# nexusqfp.net
KiCad netlist of a schematic drawn in Altium Designer
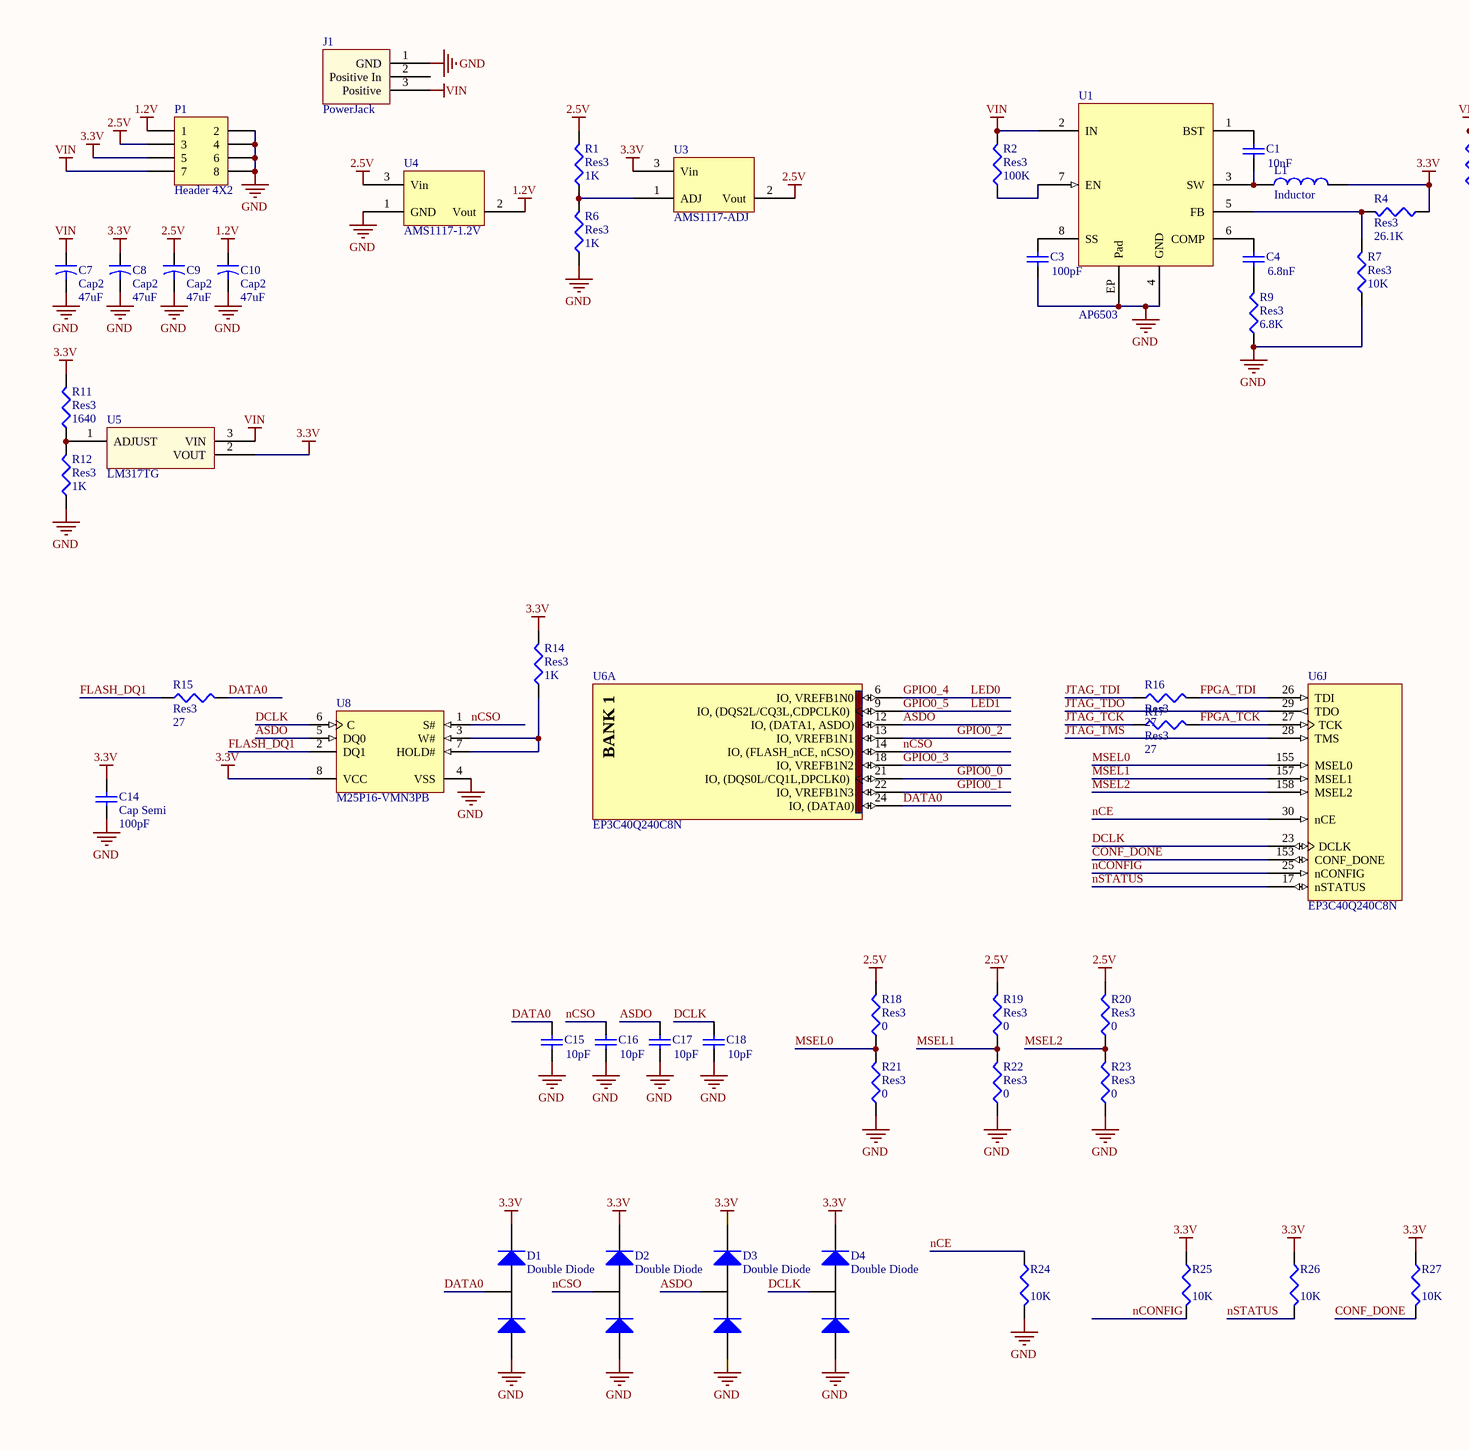
[diagram p0: nexusqfp.SchDoc, top left]
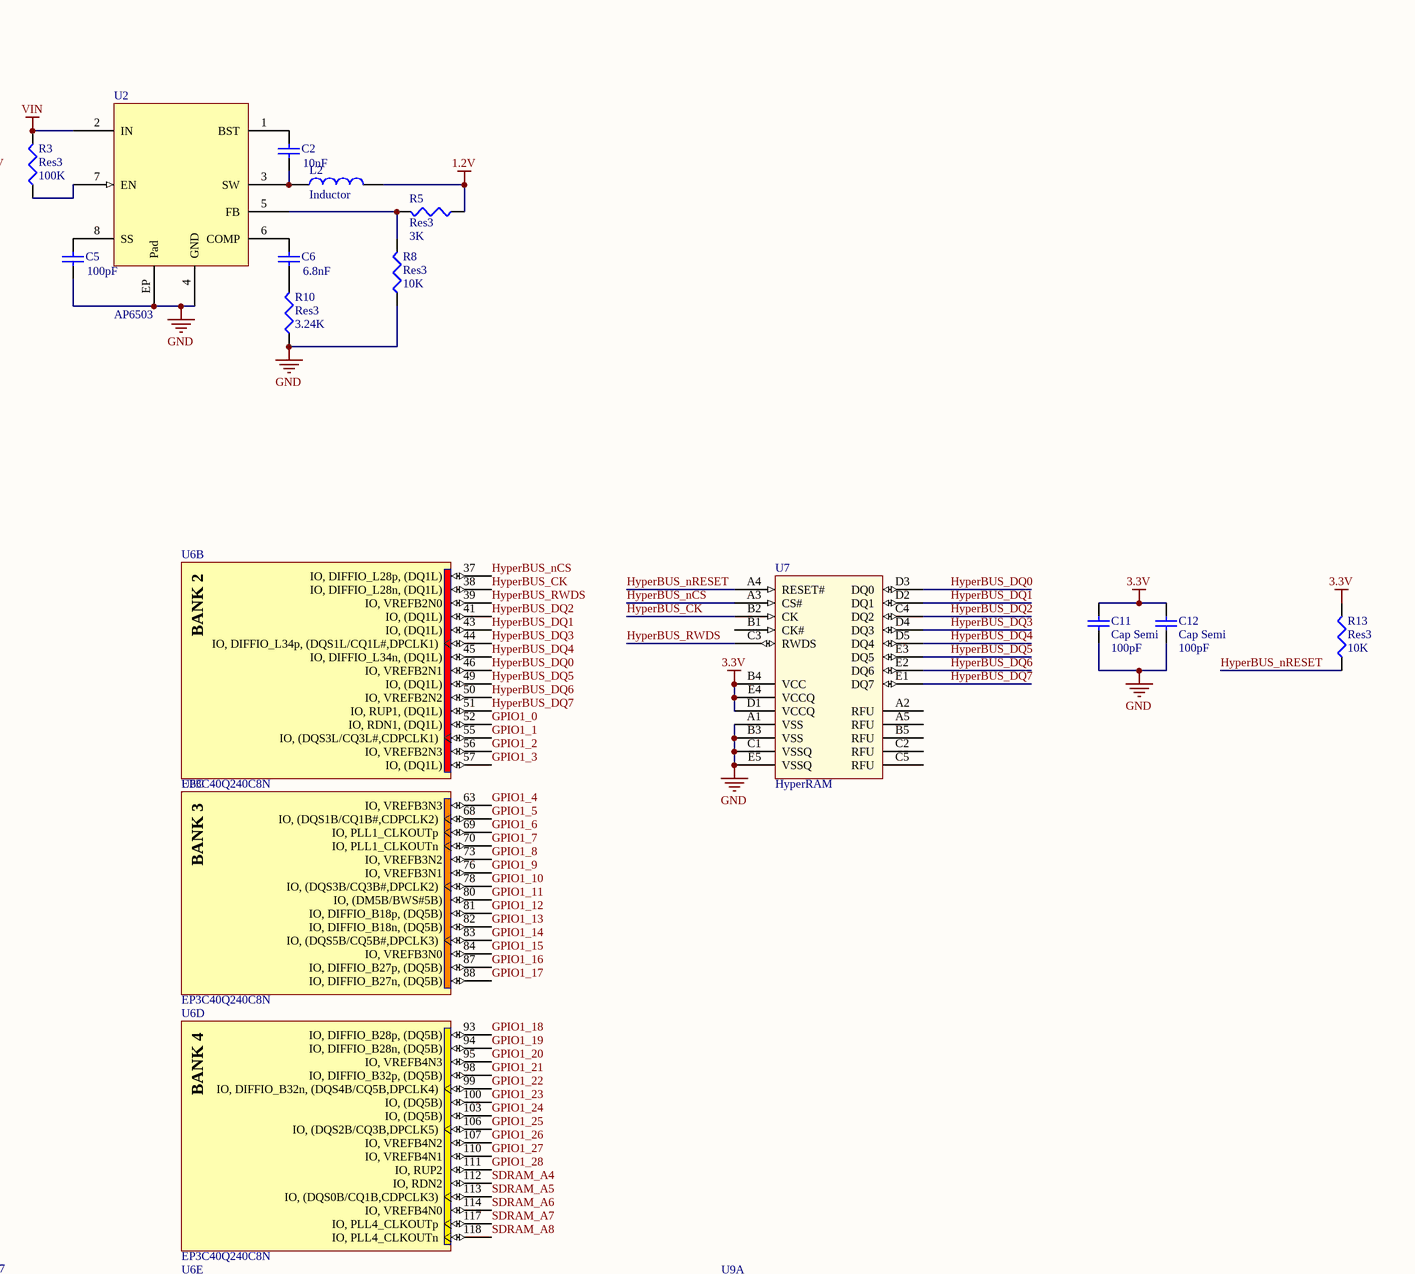
[diagram p1: nexusqfp.SchDoc, top middle]
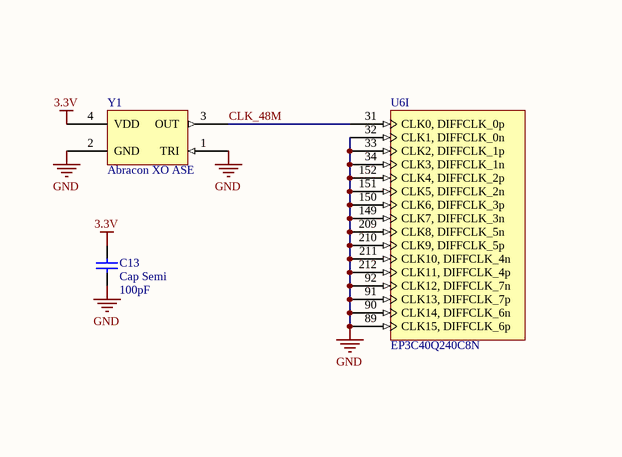
[diagram p2: nexusqfp.SchDoc, top right]
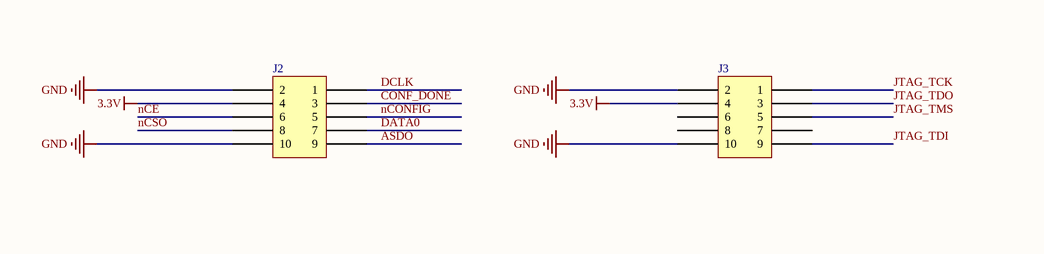
[diagram p3: nexusqfp.SchDoc, bottom left]
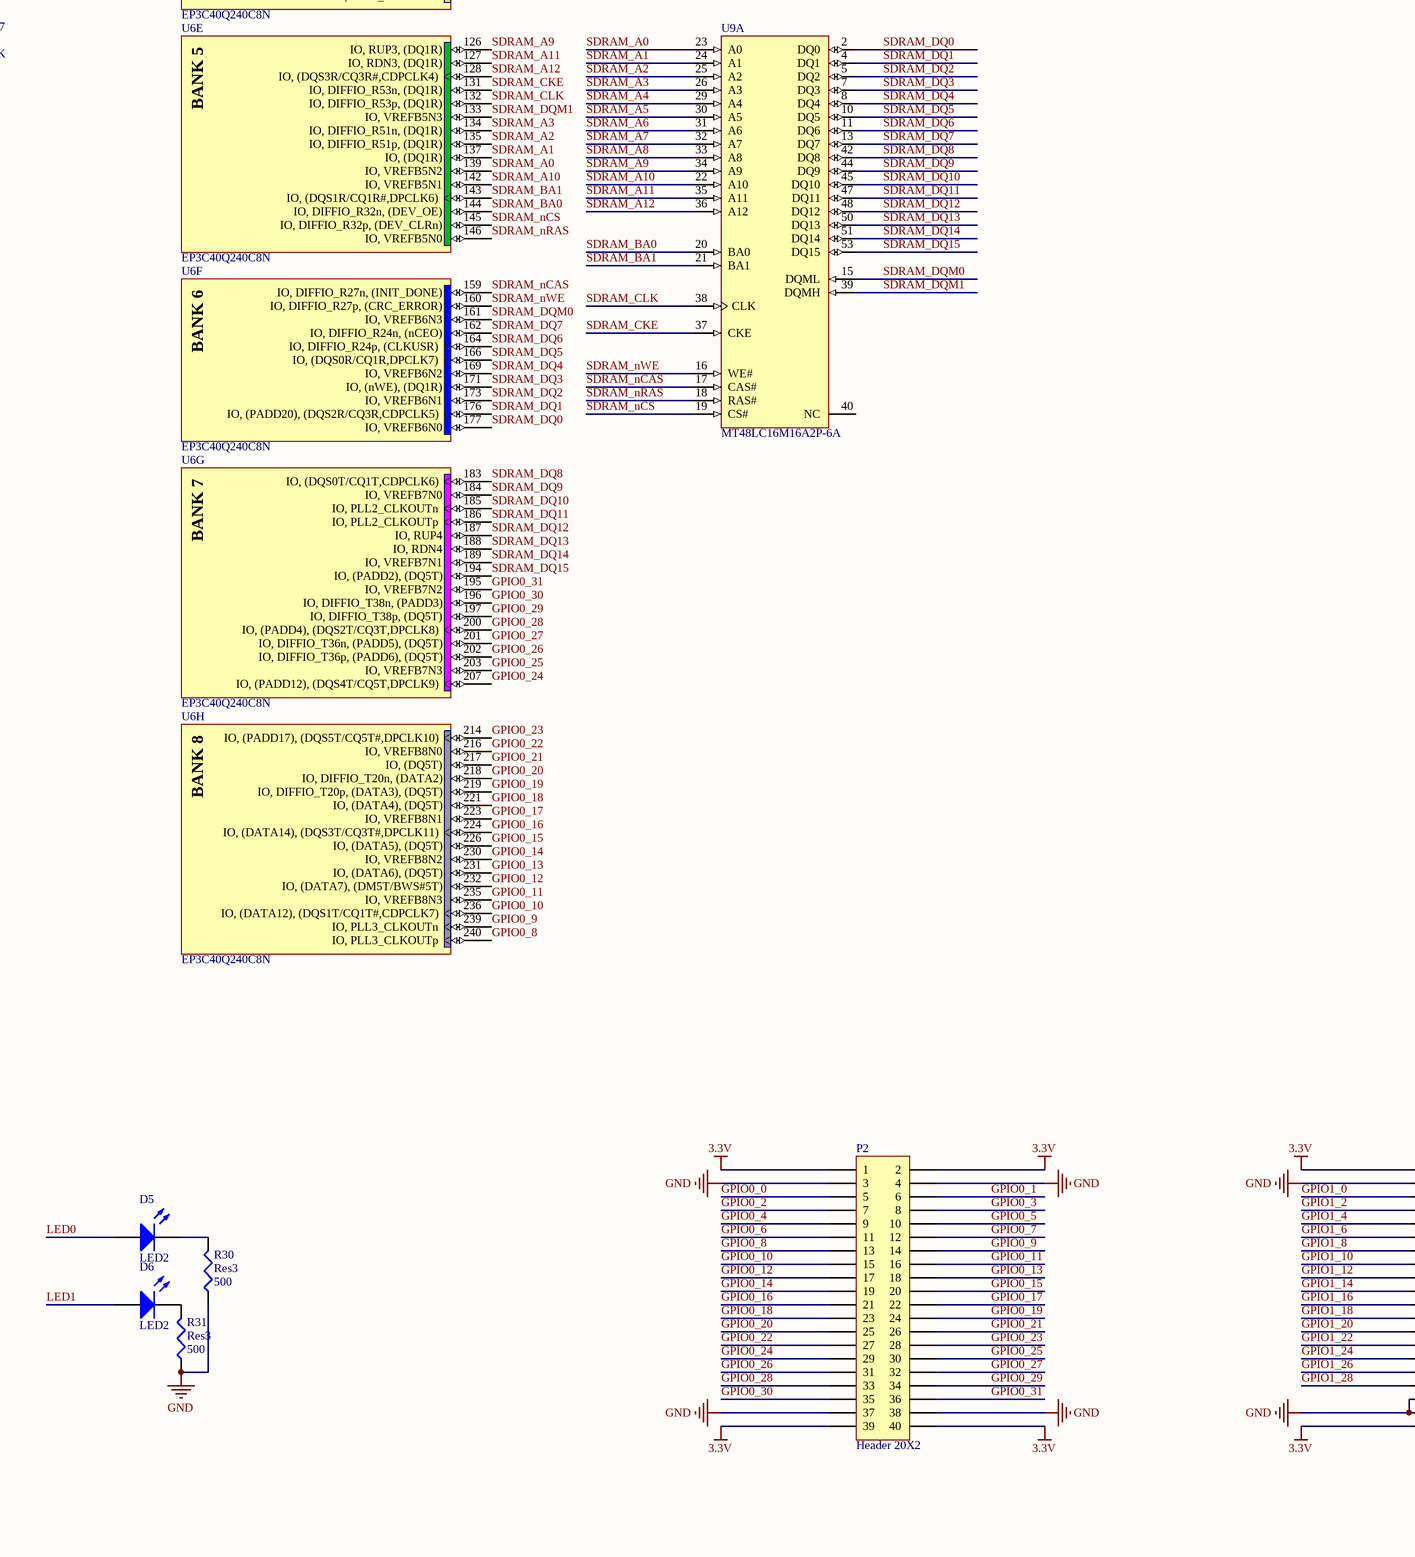
[diagram p4: nexusqfp.SchDoc, bottom middle]
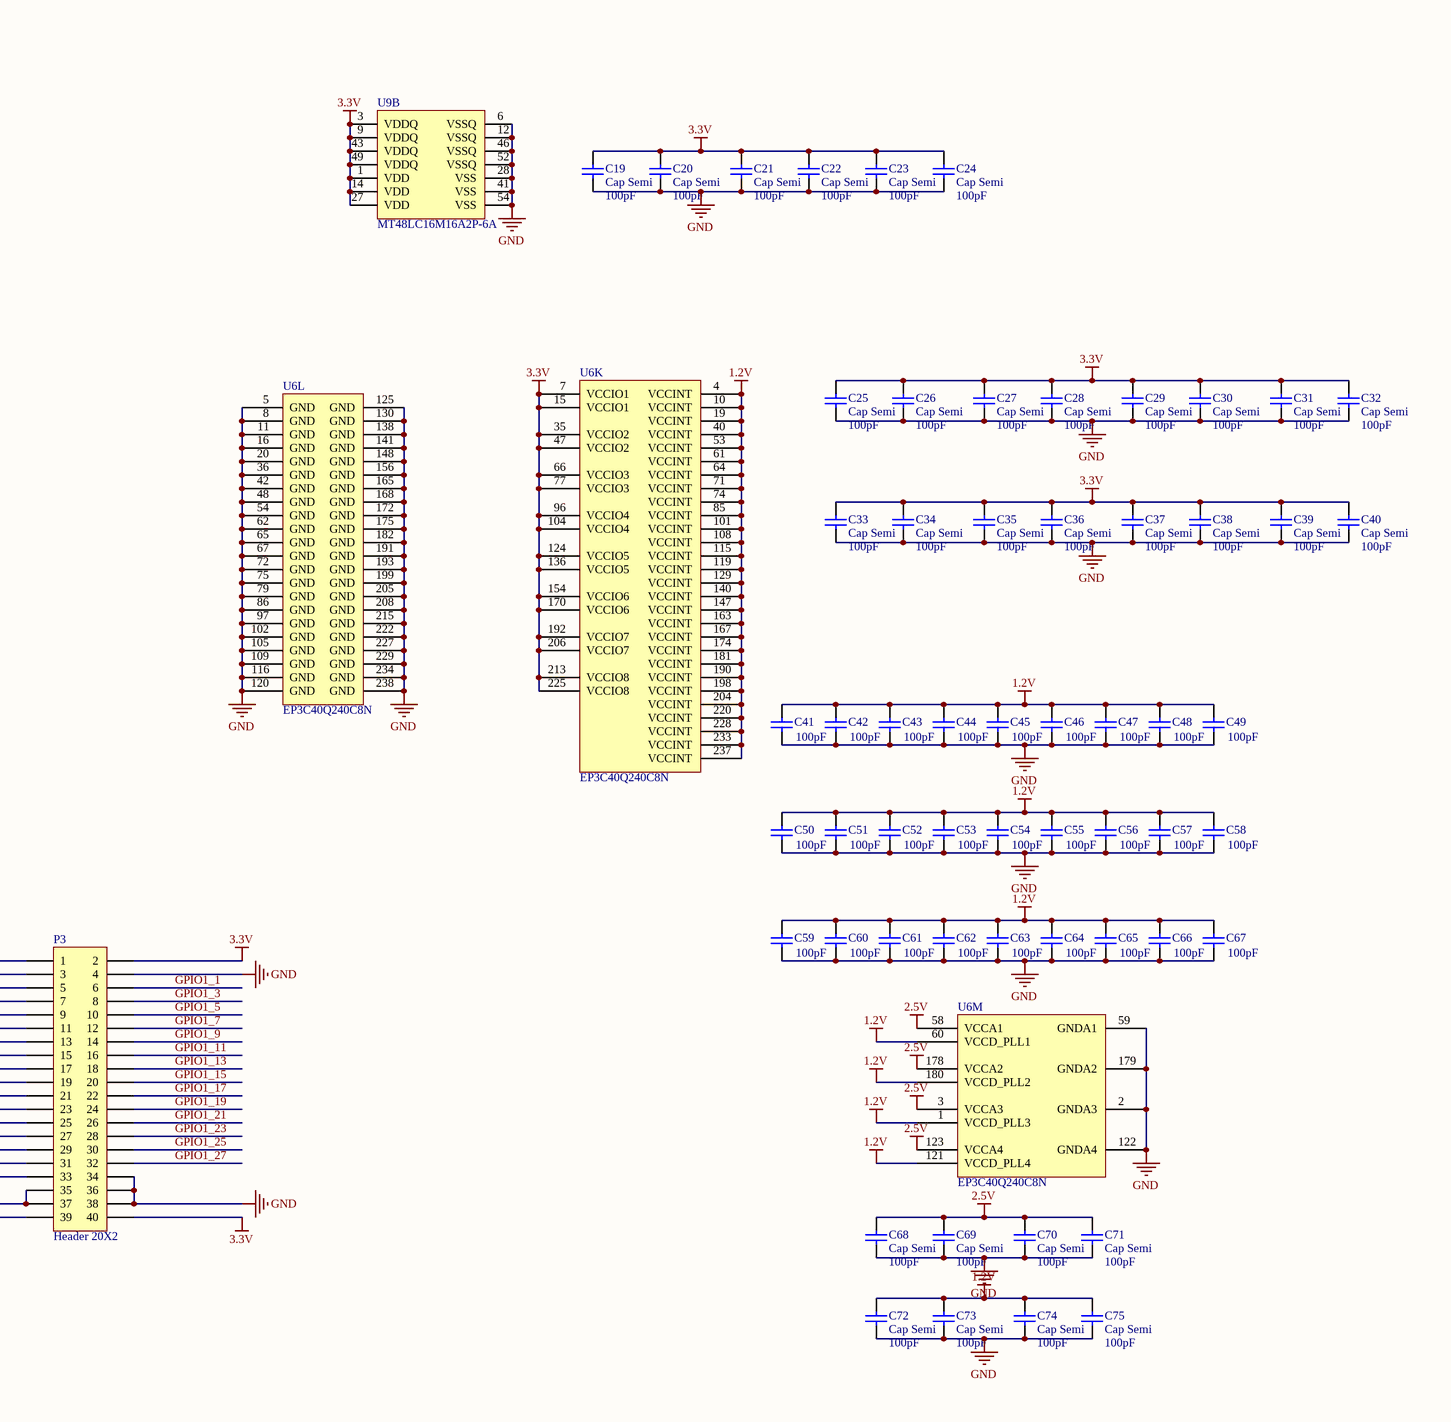
[diagram p5: nexusqfp.SchDoc, bottom right]

(export (version "E")
  (design (tool "Eeschema 10.0.6"))
  (components
    (comp (ref "C1")
      (value "10nF")
      (footprint "1608[0603]")
      (description "Capacitor (Semiconductor SIM Model)")
      (fields (field (name "Comment") "Cap Semi") (field (name "PUBLISHER") "Altium Limited"))
      (libsource (lib "Miscellaneous Devices") (part "Cap Semi"))
    )
    (comp (ref "C2")
      (value "10nF")
      (footprint "1608[0603]")
      (description "Capacitor (Semiconductor SIM Model)")
      (fields (field (name "Comment") "Cap Semi") (field (name "PUBLISHER") "Altium Limited"))
      (libsource (lib "Miscellaneous Devices") (part "Cap Semi"))
    )
    (comp (ref "C3")
      (value "100pF")
      (footprint "1608[0603]")
      (description "Capacitor (Semiconductor SIM Model)")
      (fields (field (name "Comment") "Cap Semi") (field (name "PUBLISHER") "Altium Limited"))
      (libsource (lib "Miscellaneous Devices") (part "Cap Semi"))
    )
    (comp (ref "C4")
      (value "6.8nF")
      (footprint "1608[0603]")
      (description "Capacitor (Semiconductor SIM Model)")
      (fields (field (name "Comment") "Cap Semi") (field (name "PUBLISHER") "Altium Limited"))
      (libsource (lib "Miscellaneous Devices") (part "Cap Semi"))
    )
    (comp (ref "C5")
      (value "100pF")
      (footprint "1608[0603]")
      (description "Capacitor (Semiconductor SIM Model)")
      (fields (field (name "Comment") "Cap Semi") (field (name "PUBLISHER") "Altium Limited"))
      (libsource (lib "Miscellaneous Devices") (part "Cap Semi"))
    )
    (comp (ref "C6")
      (value "6.8nF")
      (footprint "1608[0603]")
      (description "Capacitor (Semiconductor SIM Model)")
      (fields (field (name "Comment") "Cap Semi") (field (name "PUBLISHER") "Altium Limited"))
      (libsource (lib "Miscellaneous Devices") (part "Cap Semi"))
    )
    (comp (ref "C7")
      (value "Cap2")
      (footprint "CAPR5-4X5")
      (description "Capacitor")
      (fields (field (name "ALTIUM_VALUE") "47uF") (field (name "PUBLISHER") "Altium Limited"))
      (libsource (lib "Miscellaneous Devices") (part "Cap2"))
    )
    (comp (ref "C8")
      (value "Cap2")
      (footprint "CAPR5-4X5")
      (description "Capacitor")
      (fields (field (name "ALTIUM_VALUE") "47uF") (field (name "PUBLISHER") "Altium Limited"))
      (libsource (lib "Miscellaneous Devices") (part "Cap2"))
    )
    (comp (ref "C9")
      (value "Cap2")
      (footprint "CAPR5-4X5")
      (description "Capacitor")
      (fields (field (name "ALTIUM_VALUE") "47uF") (field (name "PUBLISHER") "Altium Limited"))
      (libsource (lib "Miscellaneous Devices") (part "Cap2"))
    )
    (comp (ref "C10")
      (value "Cap2")
      (footprint "CAPR5-4X5")
      (description "Capacitor")
      (fields (field (name "ALTIUM_VALUE") "47uF") (field (name "PUBLISHER") "Altium Limited"))
      (libsource (lib "Miscellaneous Devices") (part "Cap2"))
    )
    (comp (ref "C11")
      (value "Cap Semi")
      (footprint "1608[0603]")
      (description "Capacitor (Semiconductor SIM Model)")
      (fields (field (name "ALTIUM_VALUE") "100pF") (field (name "PUBLISHER") "Altium Limited"))
      (libsource (lib "Miscellaneous Devices") (part "Cap Semi"))
    )
    (comp (ref "C12")
      (value "Cap Semi")
      (footprint "1608[0603]")
      (description "Capacitor (Semiconductor SIM Model)")
      (fields (field (name "ALTIUM_VALUE") "100pF") (field (name "PUBLISHER") "Altium Limited"))
      (libsource (lib "Miscellaneous Devices") (part "Cap Semi"))
    )
    (comp (ref "C13")
      (value "Cap Semi")
      (footprint "1608[0603]")
      (description "Capacitor (Semiconductor SIM Model)")
      (fields (field (name "ALTIUM_VALUE") "100pF") (field (name "PUBLISHER") "Altium Limited"))
      (libsource (lib "Miscellaneous Devices") (part "Cap Semi"))
    )
    (comp (ref "C14")
      (value "Cap Semi")
      (footprint "1608[0603]")
      (description "Capacitor (Semiconductor SIM Model)")
      (fields (field (name "ALTIUM_VALUE") "100pF") (field (name "PUBLISHER") "Altium Limited"))
      (libsource (lib "Miscellaneous Devices") (part "Cap Semi"))
    )
    (comp (ref "C15")
      (value "10pF")
      (footprint "1608[0603]")
      (description "Capacitor (Semiconductor SIM Model)")
      (fields (field (name "PUBLISHER") "Altium Limited"))
      (libsource (lib "Miscellaneous Devices") (part "Cap Semi"))
    )
    (comp (ref "C16")
      (value "10pF")
      (footprint "1608[0603]")
      (description "Capacitor (Semiconductor SIM Model)")
      (fields (field (name "PUBLISHER") "Altium Limited"))
      (libsource (lib "Miscellaneous Devices") (part "Cap Semi"))
    )
    (comp (ref "C17")
      (value "10pF")
      (footprint "1608[0603]")
      (description "Capacitor (Semiconductor SIM Model)")
      (fields (field (name "PUBLISHER") "Altium Limited"))
      (libsource (lib "Miscellaneous Devices") (part "Cap Semi"))
    )
    (comp (ref "C18")
      (value "10pF")
      (footprint "1608[0603]")
      (description "Capacitor (Semiconductor SIM Model)")
      (fields (field (name "PUBLISHER") "Altium Limited"))
      (libsource (lib "Miscellaneous Devices") (part "Cap Semi"))
    )
    (comp (ref "C19")
      (value "Cap Semi")
      (footprint "1608[0603]")
      (description "Capacitor (Semiconductor SIM Model)")
      (fields (field (name "ALTIUM_VALUE") "100pF") (field (name "PUBLISHER") "Altium Limited"))
      (libsource (lib "Miscellaneous Devices") (part "Cap Semi"))
    )
    (comp (ref "C20")
      (value "Cap Semi")
      (footprint "1608[0603]")
      (description "Capacitor (Semiconductor SIM Model)")
      (fields (field (name "ALTIUM_VALUE") "100pF") (field (name "PUBLISHER") "Altium Limited"))
      (libsource (lib "Miscellaneous Devices") (part "Cap Semi"))
    )
    (comp (ref "C21")
      (value "Cap Semi")
      (footprint "1608[0603]")
      (description "Capacitor (Semiconductor SIM Model)")
      (fields (field (name "ALTIUM_VALUE") "100pF") (field (name "PUBLISHER") "Altium Limited"))
      (libsource (lib "Miscellaneous Devices") (part "Cap Semi"))
    )
    (comp (ref "C22")
      (value "Cap Semi")
      (footprint "1608[0603]")
      (description "Capacitor (Semiconductor SIM Model)")
      (fields (field (name "ALTIUM_VALUE") "100pF") (field (name "PUBLISHER") "Altium Limited"))
      (libsource (lib "Miscellaneous Devices") (part "Cap Semi"))
    )
    (comp (ref "C23")
      (value "Cap Semi")
      (footprint "1608[0603]")
      (description "Capacitor (Semiconductor SIM Model)")
      (fields (field (name "ALTIUM_VALUE") "100pF") (field (name "PUBLISHER") "Altium Limited"))
      (libsource (lib "Miscellaneous Devices") (part "Cap Semi"))
    )
    (comp (ref "C24")
      (value "Cap Semi")
      (footprint "1608[0603]")
      (description "Capacitor (Semiconductor SIM Model)")
      (fields (field (name "ALTIUM_VALUE") "100pF") (field (name "PUBLISHER") "Altium Limited"))
      (libsource (lib "Miscellaneous Devices") (part "Cap Semi"))
    )
    (comp (ref "C25")
      (value "Cap Semi")
      (footprint "1608[0603]")
      (description "Capacitor (Semiconductor SIM Model)")
      (fields (field (name "ALTIUM_VALUE") "100pF") (field (name "PUBLISHER") "Altium Limited"))
      (libsource (lib "Miscellaneous Devices") (part "Cap Semi"))
    )
    (comp (ref "C26")
      (value "Cap Semi")
      (footprint "1608[0603]")
      (description "Capacitor (Semiconductor SIM Model)")
      (fields (field (name "ALTIUM_VALUE") "100pF") (field (name "PUBLISHER") "Altium Limited"))
      (libsource (lib "Miscellaneous Devices") (part "Cap Semi"))
    )
    (comp (ref "C27")
      (value "Cap Semi")
      (footprint "1608[0603]")
      (description "Capacitor (Semiconductor SIM Model)")
      (fields (field (name "ALTIUM_VALUE") "100pF") (field (name "PUBLISHER") "Altium Limited"))
      (libsource (lib "Miscellaneous Devices") (part "Cap Semi"))
    )
    (comp (ref "C28")
      (value "Cap Semi")
      (footprint "1608[0603]")
      (description "Capacitor (Semiconductor SIM Model)")
      (fields (field (name "ALTIUM_VALUE") "100pF") (field (name "PUBLISHER") "Altium Limited"))
      (libsource (lib "Miscellaneous Devices") (part "Cap Semi"))
    )
    (comp (ref "C29")
      (value "Cap Semi")
      (footprint "1608[0603]")
      (description "Capacitor (Semiconductor SIM Model)")
      (fields (field (name "ALTIUM_VALUE") "100pF") (field (name "PUBLISHER") "Altium Limited"))
      (libsource (lib "Miscellaneous Devices") (part "Cap Semi"))
    )
    (comp (ref "C30")
      (value "Cap Semi")
      (footprint "1608[0603]")
      (description "Capacitor (Semiconductor SIM Model)")
      (fields (field (name "ALTIUM_VALUE") "100pF") (field (name "PUBLISHER") "Altium Limited"))
      (libsource (lib "Miscellaneous Devices") (part "Cap Semi"))
    )
    (comp (ref "C31")
      (value "Cap Semi")
      (footprint "1608[0603]")
      (description "Capacitor (Semiconductor SIM Model)")
      (fields (field (name "ALTIUM_VALUE") "100pF") (field (name "PUBLISHER") "Altium Limited"))
      (libsource (lib "Miscellaneous Devices") (part "Cap Semi"))
    )
    (comp (ref "C32")
      (value "Cap Semi")
      (footprint "1608[0603]")
      (description "Capacitor (Semiconductor SIM Model)")
      (fields (field (name "ALTIUM_VALUE") "100pF") (field (name "PUBLISHER") "Altium Limited"))
      (libsource (lib "Miscellaneous Devices") (part "Cap Semi"))
    )
    (comp (ref "C33")
      (value "Cap Semi")
      (footprint "1608[0603]")
      (description "Capacitor (Semiconductor SIM Model)")
      (fields (field (name "ALTIUM_VALUE") "100pF") (field (name "PUBLISHER") "Altium Limited"))
      (libsource (lib "Miscellaneous Devices") (part "Cap Semi"))
    )
    (comp (ref "C34")
      (value "Cap Semi")
      (footprint "1608[0603]")
      (description "Capacitor (Semiconductor SIM Model)")
      (fields (field (name "ALTIUM_VALUE") "100pF") (field (name "PUBLISHER") "Altium Limited"))
      (libsource (lib "Miscellaneous Devices") (part "Cap Semi"))
    )
    (comp (ref "C35")
      (value "Cap Semi")
      (footprint "1608[0603]")
      (description "Capacitor (Semiconductor SIM Model)")
      (fields (field (name "ALTIUM_VALUE") "100pF") (field (name "PUBLISHER") "Altium Limited"))
      (libsource (lib "Miscellaneous Devices") (part "Cap Semi"))
    )
    (comp (ref "C36")
      (value "Cap Semi")
      (footprint "1608[0603]")
      (description "Capacitor (Semiconductor SIM Model)")
      (fields (field (name "ALTIUM_VALUE") "100pF") (field (name "PUBLISHER") "Altium Limited"))
      (libsource (lib "Miscellaneous Devices") (part "Cap Semi"))
    )
    (comp (ref "C37")
      (value "Cap Semi")
      (footprint "1608[0603]")
      (description "Capacitor (Semiconductor SIM Model)")
      (fields (field (name "ALTIUM_VALUE") "100pF") (field (name "PUBLISHER") "Altium Limited"))
      (libsource (lib "Miscellaneous Devices") (part "Cap Semi"))
    )
    (comp (ref "C38")
      (value "Cap Semi")
      (footprint "1608[0603]")
      (description "Capacitor (Semiconductor SIM Model)")
      (fields (field (name "ALTIUM_VALUE") "100pF") (field (name "PUBLISHER") "Altium Limited"))
      (libsource (lib "Miscellaneous Devices") (part "Cap Semi"))
    )
    (comp (ref "C39")
      (value "Cap Semi")
      (footprint "1608[0603]")
      (description "Capacitor (Semiconductor SIM Model)")
      (fields (field (name "ALTIUM_VALUE") "100pF") (field (name "PUBLISHER") "Altium Limited"))
      (libsource (lib "Miscellaneous Devices") (part "Cap Semi"))
    )
    (comp (ref "C40")
      (value "Cap Semi")
      (footprint "1608[0603]")
      (description "Capacitor (Semiconductor SIM Model)")
      (fields (field (name "ALTIUM_VALUE") "100pF") (field (name "PUBLISHER") "Altium Limited"))
      (libsource (lib "Miscellaneous Devices") (part "Cap Semi"))
    )
    (comp (ref "C41")
      (value "100pF")
      (footprint "1608[0603]")
      (description "Capacitor (Semiconductor SIM Model)")
      (fields (field (name "Comment") "Cap Semi") (field (name "PUBLISHER") "Altium Limited"))
      (libsource (lib "Miscellaneous Devices") (part "Cap Semi"))
    )
    (comp (ref "C42")
      (value "100pF")
      (footprint "1608[0603]")
      (description "Capacitor (Semiconductor SIM Model)")
      (fields (field (name "Comment") "Cap Semi") (field (name "PUBLISHER") "Altium Limited"))
      (libsource (lib "Miscellaneous Devices") (part "Cap Semi"))
    )
    (comp (ref "C43")
      (value "100pF")
      (footprint "1608[0603]")
      (description "Capacitor (Semiconductor SIM Model)")
      (fields (field (name "Comment") "Cap Semi") (field (name "PUBLISHER") "Altium Limited"))
      (libsource (lib "Miscellaneous Devices") (part "Cap Semi"))
    )
    (comp (ref "C44")
      (value "100pF")
      (footprint "1608[0603]")
      (description "Capacitor (Semiconductor SIM Model)")
      (fields (field (name "Comment") "Cap Semi") (field (name "PUBLISHER") "Altium Limited"))
      (libsource (lib "Miscellaneous Devices") (part "Cap Semi"))
    )
    (comp (ref "C45")
      (value "100pF")
      (footprint "1608[0603]")
      (description "Capacitor (Semiconductor SIM Model)")
      (fields (field (name "Comment") "Cap Semi") (field (name "PUBLISHER") "Altium Limited"))
      (libsource (lib "Miscellaneous Devices") (part "Cap Semi"))
    )
    (comp (ref "C46")
      (value "100pF")
      (footprint "1608[0603]")
      (description "Capacitor (Semiconductor SIM Model)")
      (fields (field (name "Comment") "Cap Semi") (field (name "PUBLISHER") "Altium Limited"))
      (libsource (lib "Miscellaneous Devices") (part "Cap Semi"))
    )
    (comp (ref "C47")
      (value "100pF")
      (footprint "1608[0603]")
      (description "Capacitor (Semiconductor SIM Model)")
      (fields (field (name "Comment") "Cap Semi") (field (name "PUBLISHER") "Altium Limited"))
      (libsource (lib "Miscellaneous Devices") (part "Cap Semi"))
    )
    (comp (ref "C48")
      (value "100pF")
      (footprint "1608[0603]")
      (description "Capacitor (Semiconductor SIM Model)")
      (fields (field (name "Comment") "Cap Semi") (field (name "PUBLISHER") "Altium Limited"))
      (libsource (lib "Miscellaneous Devices") (part "Cap Semi"))
    )
    (comp (ref "C49")
      (value "100pF")
      (footprint "1608[0603]")
      (description "Capacitor (Semiconductor SIM Model)")
      (fields (field (name "Comment") "Cap Semi") (field (name "PUBLISHER") "Altium Limited"))
      (libsource (lib "Miscellaneous Devices") (part "Cap Semi"))
    )
    (comp (ref "C50")
      (value "100pF")
      (footprint "1608[0603]")
      (description "Capacitor (Semiconductor SIM Model)")
      (fields (field (name "Comment") "Cap Semi") (field (name "PUBLISHER") "Altium Limited"))
      (libsource (lib "Miscellaneous Devices") (part "Cap Semi"))
    )
    (comp (ref "C51")
      (value "100pF")
      (footprint "1608[0603]")
      (description "Capacitor (Semiconductor SIM Model)")
      (fields (field (name "Comment") "Cap Semi") (field (name "PUBLISHER") "Altium Limited"))
      (libsource (lib "Miscellaneous Devices") (part "Cap Semi"))
    )
    (comp (ref "C52")
      (value "100pF")
      (footprint "1608[0603]")
      (description "Capacitor (Semiconductor SIM Model)")
      (fields (field (name "Comment") "Cap Semi") (field (name "PUBLISHER") "Altium Limited"))
      (libsource (lib "Miscellaneous Devices") (part "Cap Semi"))
    )
    (comp (ref "C53")
      (value "100pF")
      (footprint "1608[0603]")
      (description "Capacitor (Semiconductor SIM Model)")
      (fields (field (name "Comment") "Cap Semi") (field (name "PUBLISHER") "Altium Limited"))
      (libsource (lib "Miscellaneous Devices") (part "Cap Semi"))
    )
    (comp (ref "C54")
      (value "100pF")
      (footprint "1608[0603]")
      (description "Capacitor (Semiconductor SIM Model)")
      (fields (field (name "Comment") "Cap Semi") (field (name "PUBLISHER") "Altium Limited"))
      (libsource (lib "Miscellaneous Devices") (part "Cap Semi"))
    )
    (comp (ref "C55")
      (value "100pF")
      (footprint "1608[0603]")
      (description "Capacitor (Semiconductor SIM Model)")
      (fields (field (name "Comment") "Cap Semi") (field (name "PUBLISHER") "Altium Limited"))
      (libsource (lib "Miscellaneous Devices") (part "Cap Semi"))
    )
    (comp (ref "C56")
      (value "100pF")
      (footprint "1608[0603]")
      (description "Capacitor (Semiconductor SIM Model)")
      (fields (field (name "Comment") "Cap Semi") (field (name "PUBLISHER") "Altium Limited"))
      (libsource (lib "Miscellaneous Devices") (part "Cap Semi"))
    )
    (comp (ref "C57")
      (value "100pF")
      (footprint "1608[0603]")
      (description "Capacitor (Semiconductor SIM Model)")
      (fields (field (name "Comment") "Cap Semi") (field (name "PUBLISHER") "Altium Limited"))
      (libsource (lib "Miscellaneous Devices") (part "Cap Semi"))
    )
    (comp (ref "C58")
      (value "100pF")
      (footprint "1608[0603]")
      (description "Capacitor (Semiconductor SIM Model)")
      (fields (field (name "Comment") "Cap Semi") (field (name "PUBLISHER") "Altium Limited"))
      (libsource (lib "Miscellaneous Devices") (part "Cap Semi"))
    )
    (comp (ref "C59")
      (value "100pF")
      (footprint "1608[0603]")
      (description "Capacitor (Semiconductor SIM Model)")
      (fields (field (name "Comment") "Cap Semi") (field (name "PUBLISHER") "Altium Limited"))
      (libsource (lib "Miscellaneous Devices") (part "Cap Semi"))
    )
    (comp (ref "C60")
      (value "100pF")
      (footprint "1608[0603]")
      (description "Capacitor (Semiconductor SIM Model)")
      (fields (field (name "Comment") "Cap Semi") (field (name "PUBLISHER") "Altium Limited"))
      (libsource (lib "Miscellaneous Devices") (part "Cap Semi"))
    )
    (comp (ref "C61")
      (value "100pF")
      (footprint "1608[0603]")
      (description "Capacitor (Semiconductor SIM Model)")
      (fields (field (name "Comment") "Cap Semi") (field (name "PUBLISHER") "Altium Limited"))
      (libsource (lib "Miscellaneous Devices") (part "Cap Semi"))
    )
    (comp (ref "C62")
      (value "100pF")
      (footprint "1608[0603]")
      (description "Capacitor (Semiconductor SIM Model)")
      (fields (field (name "Comment") "Cap Semi") (field (name "PUBLISHER") "Altium Limited"))
      (libsource (lib "Miscellaneous Devices") (part "Cap Semi"))
    )
    (comp (ref "C63")
      (value "100pF")
      (footprint "1608[0603]")
      (description "Capacitor (Semiconductor SIM Model)")
      (fields (field (name "Comment") "Cap Semi") (field (name "PUBLISHER") "Altium Limited"))
      (libsource (lib "Miscellaneous Devices") (part "Cap Semi"))
    )
    (comp (ref "C64")
      (value "100pF")
      (footprint "1608[0603]")
      (description "Capacitor (Semiconductor SIM Model)")
      (fields (field (name "Comment") "Cap Semi") (field (name "PUBLISHER") "Altium Limited"))
      (libsource (lib "Miscellaneous Devices") (part "Cap Semi"))
    )
    (comp (ref "C65")
      (value "100pF")
      (footprint "1608[0603]")
      (description "Capacitor (Semiconductor SIM Model)")
      (fields (field (name "Comment") "Cap Semi") (field (name "PUBLISHER") "Altium Limited"))
      (libsource (lib "Miscellaneous Devices") (part "Cap Semi"))
    )
    (comp (ref "C66")
      (value "100pF")
      (footprint "1608[0603]")
      (description "Capacitor (Semiconductor SIM Model)")
      (fields (field (name "Comment") "Cap Semi") (field (name "PUBLISHER") "Altium Limited"))
      (libsource (lib "Miscellaneous Devices") (part "Cap Semi"))
    )
    (comp (ref "C67")
      (value "100pF")
      (footprint "1608[0603]")
      (description "Capacitor (Semiconductor SIM Model)")
      (fields (field (name "Comment") "Cap Semi") (field (name "PUBLISHER") "Altium Limited"))
      (libsource (lib "Miscellaneous Devices") (part "Cap Semi"))
    )
    (comp (ref "C68")
      (value "Cap Semi")
      (footprint "1608[0603]")
      (description "Capacitor (Semiconductor SIM Model)")
      (fields (field (name "ALTIUM_VALUE") "100pF") (field (name "PUBLISHER") "Altium Limited"))
      (libsource (lib "Miscellaneous Devices") (part "Cap Semi"))
    )
    (comp (ref "C69")
      (value "Cap Semi")
      (footprint "1608[0603]")
      (description "Capacitor (Semiconductor SIM Model)")
      (fields (field (name "ALTIUM_VALUE") "100pF") (field (name "PUBLISHER") "Altium Limited"))
      (libsource (lib "Miscellaneous Devices") (part "Cap Semi"))
    )
    (comp (ref "C70")
      (value "Cap Semi")
      (footprint "1608[0603]")
      (description "Capacitor (Semiconductor SIM Model)")
      (fields (field (name "ALTIUM_VALUE") "100pF") (field (name "PUBLISHER") "Altium Limited"))
      (libsource (lib "Miscellaneous Devices") (part "Cap Semi"))
    )
    (comp (ref "C71")
      (value "Cap Semi")
      (footprint "1608[0603]")
      (description "Capacitor (Semiconductor SIM Model)")
      (fields (field (name "ALTIUM_VALUE") "100pF") (field (name "PUBLISHER") "Altium Limited"))
      (libsource (lib "Miscellaneous Devices") (part "Cap Semi"))
    )
    (comp (ref "C72")
      (value "Cap Semi")
      (footprint "1608[0603]")
      (description "Capacitor (Semiconductor SIM Model)")
      (fields (field (name "ALTIUM_VALUE") "100pF") (field (name "PUBLISHER") "Altium Limited"))
      (libsource (lib "Miscellaneous Devices") (part "Cap Semi"))
    )
    (comp (ref "C73")
      (value "Cap Semi")
      (footprint "1608[0603]")
      (description "Capacitor (Semiconductor SIM Model)")
      (fields (field (name "ALTIUM_VALUE") "100pF") (field (name "PUBLISHER") "Altium Limited"))
      (libsource (lib "Miscellaneous Devices") (part "Cap Semi"))
    )
    (comp (ref "C74")
      (value "Cap Semi")
      (footprint "1608[0603]")
      (description "Capacitor (Semiconductor SIM Model)")
      (fields (field (name "ALTIUM_VALUE") "100pF") (field (name "PUBLISHER") "Altium Limited"))
      (libsource (lib "Miscellaneous Devices") (part "Cap Semi"))
    )
    (comp (ref "C75")
      (value "Cap Semi")
      (footprint "1608[0603]")
      (description "Capacitor (Semiconductor SIM Model)")
      (fields (field (name "ALTIUM_VALUE") "100pF") (field (name "PUBLISHER") "Altium Limited"))
      (libsource (lib "Miscellaneous Devices") (part "Cap Semi"))
    )
    (comp (ref "D1") (value "Double Diode") (footprint "SOT-23") (libsource (lib "BAT54S") (part "BAT54S")))
    (comp (ref "D2") (value "Double Diode") (footprint "SOT-23") (libsource (lib "BAT54S") (part "BAT54S")))
    (comp (ref "D3") (value "Double Diode") (footprint "SOT-23") (libsource (lib "BAT54S") (part "BAT54S")))
    (comp (ref "D4") (value "Double Diode") (footprint "SOT-23") (libsource (lib "BAT54S") (part "BAT54S")))
    (comp (ref "D5")
      (value "LED2")
      (footprint "3.2X1.6X1.1")
      (description "Typical RED, GREEN, YELLOW, AMBER GaAs LED")
      (fields (field (name "PUBLISHER") "Altium Limited"))
      (libsource (lib "Miscellaneous Devices") (part "LED2"))
    )
    (comp (ref "D6")
      (value "LED2")
      (footprint "3.2X1.6X1.1")
      (description "Typical RED, GREEN, YELLOW, AMBER GaAs LED")
      (fields (field (name "PUBLISHER") "Altium Limited"))
      (libsource (lib "Miscellaneous Devices") (part "LED2"))
    )
    (comp (ref "J1")
      (value "PowerJack")
      (footprint "PJ-002A")
      (libsource (lib "PowerJack") (part "PowerJack"))
    )
    (comp (ref "J2")
      (value "2X5 2.54mm Conn with polarity")
      (footprint "2X5 with polarity")
      (libsource (lib "Corner") (part "2X5 2.54mm Conn with polarity"))
    )
    (comp (ref "J3")
      (value "2X5 2.54mm Conn with polarity")
      (footprint "2X5 with polarity")
      (libsource (lib "Corner") (part "2X5 2.54mm Conn with polarity"))
    )
    (comp (ref "L1")
      (value "Inductor")
      (footprint "74477110 Inductor")
      (libsource (lib "Inductor") (part "Inductor"))
    )
    (comp (ref "L2")
      (value "Inductor")
      (footprint "744311330")
      (libsource (lib "Inductor") (part "Inductor"))
    )
    (comp (ref "P1")
      (value "Header 4X2")
      (footprint "HDR2X4")
      (description "Header, 4-Pin, Dual row")
      (fields (field (name "PUBLISHER") "Altium Limited"))
      (libsource (lib "Miscellaneous Connectors") (part "Header 4X2"))
    )
    (comp (ref "P2")
      (value "Header 20X2")
      (footprint "HDR2X20")
      (description "Header, 20-Pin, Dual row")
      (fields (field (name "PUBLISHER") "Altium Limited"))
      (libsource (lib "Miscellaneous Connectors") (part "Header 20X2"))
    )
    (comp (ref "P3")
      (value "Header 20X2")
      (footprint "HDR2X20")
      (description "Header, 20-Pin, Dual row")
      (fields (field (name "PUBLISHER") "Altium Limited"))
      (libsource (lib "Miscellaneous Connectors") (part "Header 20X2"))
    )
    (comp (ref "R1")
      (value "Res3")
      (footprint "J1-0603")
      (description "Resistor")
      (fields (field (name "ALTIUM_VALUE") "1K") (field (name "PUBLISHER") "Altium Limited"))
      (libsource (lib "Miscellaneous Devices") (part "Res3"))
    )
    (comp (ref "R2")
      (value "Res3")
      (footprint "J1-0603")
      (description "Resistor")
      (fields (field (name "ALTIUM_VALUE") "100K") (field (name "PUBLISHER") "Altium Limited"))
      (libsource (lib "Miscellaneous Devices") (part "Res3"))
    )
    (comp (ref "R3")
      (value "Res3")
      (footprint "J1-0603")
      (description "Resistor")
      (fields (field (name "ALTIUM_VALUE") "100K") (field (name "PUBLISHER") "Altium Limited"))
      (libsource (lib "Miscellaneous Devices") (part "Res3"))
    )
    (comp (ref "R4")
      (value "Res3")
      (footprint "J1-0603")
      (description "Resistor")
      (fields (field (name "ALTIUM_VALUE") "26.1K") (field (name "PUBLISHER") "Altium Limited"))
      (libsource (lib "Miscellaneous Devices") (part "Res3"))
    )
    (comp (ref "R5")
      (value "Res3")
      (footprint "J1-0603")
      (description "Resistor")
      (fields (field (name "ALTIUM_VALUE") "3K") (field (name "PUBLISHER") "Altium Limited"))
      (libsource (lib "Miscellaneous Devices") (part "Res3"))
    )
    (comp (ref "R6")
      (value "Res3")
      (footprint "J1-0603")
      (description "Resistor")
      (fields (field (name "ALTIUM_VALUE") "1K") (field (name "PUBLISHER") "Altium Limited"))
      (libsource (lib "Miscellaneous Devices") (part "Res3"))
    )
    (comp (ref "R7")
      (value "Res3")
      (footprint "J1-0603")
      (description "Resistor")
      (fields (field (name "ALTIUM_VALUE") "10K") (field (name "PUBLISHER") "Altium Limited"))
      (libsource (lib "Miscellaneous Devices") (part "Res3"))
    )
    (comp (ref "R8")
      (value "Res3")
      (footprint "J1-0603")
      (description "Resistor")
      (fields (field (name "ALTIUM_VALUE") "10K") (field (name "PUBLISHER") "Altium Limited"))
      (libsource (lib "Miscellaneous Devices") (part "Res3"))
    )
    (comp (ref "R9")
      (value "Res3")
      (footprint "J1-0603")
      (description "Resistor")
      (fields (field (name "ALTIUM_VALUE") "6.8K") (field (name "PUBLISHER") "Altium Limited"))
      (libsource (lib "Miscellaneous Devices") (part "Res3"))
    )
    (comp (ref "R10")
      (value "Res3")
      (footprint "J1-0603")
      (description "Resistor")
      (fields (field (name "ALTIUM_VALUE") "3.24K") (field (name "PUBLISHER") "Altium Limited"))
      (libsource (lib "Miscellaneous Devices") (part "Res3"))
    )
    (comp (ref "R11")
      (value "Res3")
      (footprint "J1-0603")
      (description "Resistor")
      (fields (field (name "ALTIUM_VALUE") "1640") (field (name "PUBLISHER") "Altium Limited"))
      (libsource (lib "Miscellaneous Devices") (part "Res3"))
    )
    (comp (ref "R12")
      (value "Res3")
      (footprint "J1-0603")
      (description "Resistor")
      (fields (field (name "ALTIUM_VALUE") "1K") (field (name "PUBLISHER") "Altium Limited"))
      (libsource (lib "Miscellaneous Devices") (part "Res3"))
    )
    (comp (ref "R13")
      (value "Res3")
      (footprint "J1-0603")
      (description "Resistor")
      (fields (field (name "ALTIUM_VALUE") "10K") (field (name "PUBLISHER") "Altium Limited"))
      (libsource (lib "Miscellaneous Devices") (part "Res3"))
    )
    (comp (ref "R14")
      (value "Res3")
      (footprint "J1-0603")
      (description "Resistor")
      (fields (field (name "ALTIUM_VALUE") "1K") (field (name "PUBLISHER") "Altium Limited"))
      (libsource (lib "Miscellaneous Devices") (part "Res3"))
    )
    (comp (ref "R15")
      (value "Res3")
      (footprint "J1-0603")
      (description "Resistor")
      (fields (field (name "ALTIUM_VALUE") "27") (field (name "PUBLISHER") "Altium Limited"))
      (libsource (lib "Miscellaneous Devices") (part "Res3"))
    )
    (comp (ref "R16")
      (value "Res3")
      (footprint "J1-0603")
      (description "Resistor")
      (fields (field (name "ALTIUM_VALUE") "27") (field (name "PUBLISHER") "Altium Limited"))
      (libsource (lib "Miscellaneous Devices") (part "Res3"))
    )
    (comp (ref "R17")
      (value "Res3")
      (footprint "J1-0603")
      (description "Resistor")
      (fields (field (name "ALTIUM_VALUE") "27") (field (name "PUBLISHER") "Altium Limited"))
      (libsource (lib "Miscellaneous Devices") (part "Res3"))
    )
    (comp (ref "R18")
      (value "Res3")
      (footprint "J1-0603")
      (description "Resistor")
      (fields (field (name "ALTIUM_VALUE") "0") (field (name "PUBLISHER") "Altium Limited"))
      (libsource (lib "Miscellaneous Devices") (part "Res3"))
    )
    (comp (ref "R19")
      (value "Res3")
      (footprint "J1-0603")
      (description "Resistor")
      (fields (field (name "ALTIUM_VALUE") "0") (field (name "PUBLISHER") "Altium Limited"))
      (libsource (lib "Miscellaneous Devices") (part "Res3"))
    )
    (comp (ref "R20")
      (value "Res3")
      (footprint "J1-0603")
      (description "Resistor")
      (fields (field (name "ALTIUM_VALUE") "0") (field (name "PUBLISHER") "Altium Limited"))
      (libsource (lib "Miscellaneous Devices") (part "Res3"))
    )
    (comp (ref "R21")
      (value "Res3")
      (footprint "J1-0603")
      (description "Resistor")
      (fields (field (name "ALTIUM_VALUE") "0") (field (name "PUBLISHER") "Altium Limited"))
      (libsource (lib "Miscellaneous Devices") (part "Res3"))
    )
    (comp (ref "R22")
      (value "Res3")
      (footprint "J1-0603")
      (description "Resistor")
      (fields (field (name "ALTIUM_VALUE") "0") (field (name "PUBLISHER") "Altium Limited"))
      (libsource (lib "Miscellaneous Devices") (part "Res3"))
    )
    (comp (ref "R23")
      (value "Res3")
      (footprint "J1-0603")
      (description "Resistor")
      (fields (field (name "ALTIUM_VALUE") "0") (field (name "PUBLISHER") "Altium Limited"))
      (libsource (lib "Miscellaneous Devices") (part "Res3"))
    )
    (comp (ref "R24")
      (value "10K")
      (footprint "J1-0603")
      (description "Resistor")
      (fields (field (name "Comment") "Res3") (field (name "PUBLISHER") "Altium Limited"))
      (libsource (lib "Miscellaneous Devices") (part "Res3"))
    )
    (comp (ref "R25")
      (value "10K")
      (footprint "J1-0603")
      (description "Resistor")
      (fields (field (name "Comment") "Res3") (field (name "PUBLISHER") "Altium Limited"))
      (libsource (lib "Miscellaneous Devices") (part "Res3"))
    )
    (comp (ref "R26")
      (value "10K")
      (footprint "J1-0603")
      (description "Resistor")
      (fields (field (name "Comment") "Res3") (field (name "PUBLISHER") "Altium Limited"))
      (libsource (lib "Miscellaneous Devices") (part "Res3"))
    )
    (comp (ref "R27")
      (value "10K")
      (footprint "J1-0603")
      (description "Resistor")
      (fields (field (name "Comment") "Res3") (field (name "PUBLISHER") "Altium Limited"))
      (libsource (lib "Miscellaneous Devices") (part "Res3"))
    )
    (comp (ref "R30")
      (value "Res3")
      (footprint "J1-0603")
      (description "Resistor")
      (fields (field (name "ALTIUM_VALUE") "500") (field (name "PUBLISHER") "Altium Limited"))
      (libsource (lib "Miscellaneous Devices") (part "Res3"))
    )
    (comp (ref "R31")
      (value "Res3")
      (footprint "J1-0603")
      (description "Resistor")
      (fields (field (name "ALTIUM_VALUE") "500") (field (name "PUBLISHER") "Altium Limited"))
      (libsource (lib "Miscellaneous Devices") (part "Res3"))
    )
    (comp (ref "U1") (value "AP6503") (footprint "SO-8EP") (libsource (lib "AP6503") (part "AP6503")))
    (comp (ref "U2") (value "AP6503") (footprint "SO-8EP") (libsource (lib "AP6503") (part "AP6503")))
    (comp (ref "U3")
      (value "AMS1117-ADJ")
      (footprint "SOT-223")
      (libsource (lib "AMS1117") (part "AMS1117-ADJ"))
    )
    (comp (ref "U4")
      (value "AMS1117-1.2V")
      (footprint "SOT-223")
      (libsource (lib "AMS1117") (part "AMS1117-1.2V"))
    )
    (comp (ref "U5")
      (value "LM317TG")
      (footprint "TO-220AB")
      (description "Imported")
      (libsource (lib "lm317") (part "LM317TG"))
    )
    (comp (ref "U6")
      (value "EP3C40Q240C8N")
      (footprint "PQFP240_N")
      (fields (field (name "PUBLISHER") "Altium Limited"))
      (libsource (lib "Altera Cyclone III") (part "EP3C40Q240C8N"))
    )
    (comp (ref "U7")
      (value "HyperRAM")
      (footprint "BGA5x5 1mm")
      (libsource (lib "HyperRAM") (part "HyperRAM"))
    )
    (comp (ref "U8")
      (value "M25P16-VMN3PB")
      (footprint "MICT-MN-8_N")
      (description "16 Mb (x1) Automotive Serial NOR Flash Memory, 75 MHz, 2.7 to 3.6 V, 8-pin SO8 Narrow (MN), Tube")
      (fields (field (name "VOLTAGE") "2.7V-3.6V ") (field (name "MANUFACTURER") "Micron"))
      (libsource (lib "Micron Memory Serial NOR Flash") (part "M25P16-VMN3PB"))
    )
    (comp (ref "U9")
      (value "MT48LC16M16A2P-6A")
      (footprint "MICT-P-54_N")
      (description "256Mb PC133 SDR SDRAM, 16Mb x 16, 6ns, 3.3V, 0 to 70 degC, 54-Pin TSOP, Pb-Free")
      (fields (field (name "VOLTAGE") "3.3V ") (field (name "MANUFACTURER") "Micron"))
      (libsource (lib "Micron Memory SDRAM") (part "MT48LC16M16A2P-6A"))
    )
    (comp (ref "Y1")
      (value "Abracon XO ASE")
      (footprint "ABRACON ASE")
      (description "SMD CMOS Crystal Oscillator")
      (libsource (lib "ABRACON ASE") (part "Abracon XO ASE"))
    )
  )
  (nets
    (net (code "1") (name "/ASDO") (class "Default")
      (node (ref "C17") (pin "1") (pinfunction "1_1") (pintype "passive"))
      (node (ref "D3") (pin "3") (pintype "passive"))
      (node (ref "J2") (pin "9") (pinfunction "9_9") (pintype "passive"))
      (node (ref "U6") (pin "12") (pinfunction "IO,_(DATA1,_ASDO)_12") (pintype "bidirectional"))
      (node (ref "U8") (pin "5") (pinfunction "DQ0_5") (pintype "input"))
    )
    (net (code "2") (name "/CLK_48M") (class "Default")
      (node (ref "U6") (pin "31") (pinfunction "CLK0,_DIFFCLK_0p_31") (pintype "input"))
      (node (ref "Y1") (pin "3") (pinfunction "OUT_3") (pintype "output"))
    )
    (net (code "3") (name "/CONF_DONE") (class "Default")
      (node (ref "J2") (pin "3") (pinfunction "3_3") (pintype "passive"))
      (node (ref "R27") (pin "2") (pinfunction "2_2") (pintype "passive"))
      (node (ref "U6") (pin "153") (pinfunction "CONF_DONE_153") (pintype "bidirectional"))
    )
    (net (code "4") (name "/DATA0") (class "Default")
      (node (ref "C15") (pin "1") (pinfunction "1_1") (pintype "passive"))
      (node (ref "D1") (pin "3") (pintype "passive"))
      (node (ref "J2") (pin "7") (pinfunction "7_7") (pintype "passive"))
      (node (ref "R15") (pin "2") (pinfunction "2_2") (pintype "passive"))
      (node (ref "U6") (pin "24") (pinfunction "IO,_(DATA0)_24") (pintype "bidirectional"))
    )
    (net (code "5") (name "/DCLK") (class "Default")
      (node (ref "C18") (pin "1") (pinfunction "1_1") (pintype "passive"))
      (node (ref "D4") (pin "3") (pintype "passive"))
      (node (ref "J2") (pin "1") (pinfunction "1_1") (pintype "passive"))
      (node (ref "U6") (pin "23") (pinfunction "DCLK_23") (pintype "bidirectional"))
      (node (ref "U8") (pin "6") (pinfunction "C_6") (pintype "input"))
    )
    (net (code "6") (name "/FLASH_DQ1") (class "Default")
      (node (ref "R15") (pin "1") (pinfunction "1_1") (pintype "passive"))
      (node (ref "U8") (pin "2") (pinfunction "DQ1_2") (pintype "tri_state"))
    )
    (net (code "7") (name "/FPGA_TCK") (class "Default")
      (node (ref "R17") (pin "2") (pinfunction "2_2") (pintype "passive"))
      (node (ref "U6") (pin "27") (pinfunction "TCK_27") (pintype "input"))
    )
    (net (code "8") (name "/FPGA_TDI") (class "Default")
      (node (ref "R16") (pin "2") (pinfunction "2_2") (pintype "passive"))
      (node (ref "U6") (pin "26") (pinfunction "TDI_26") (pintype "input"))
    )
    (net (code "9") (name "/GPIO0_0") (class "Default")
      (node (ref "P2") (pin "5") (pinfunction "5_5") (pintype "passive"))
      (node (ref "U6") (pin "21") (pinfunction "IO,_(DQS0L/CQ1L,DPCLK0)_21") (pintype "bidirectional"))
    )
    (net (code "10") (name "/GPIO0_1") (class "Default")
      (node (ref "P2") (pin "6") (pinfunction "6_6") (pintype "passive"))
      (node (ref "U6") (pin "22") (pinfunction "IO,_VREFB1N3_22") (pintype "bidirectional"))
    )
    (net (code "11") (name "/GPIO0_2") (class "Default")
      (node (ref "P2") (pin "7") (pinfunction "7_7") (pintype "passive"))
      (node (ref "U6") (pin "13") (pinfunction "IO,_VREFB1N1_13") (pintype "bidirectional"))
    )
    (net (code "12") (name "/GPIO0_3") (class "Default")
      (node (ref "P2") (pin "8") (pinfunction "8_8") (pintype "passive"))
      (node (ref "U6") (pin "18") (pinfunction "IO,_VREFB1N2_18") (pintype "bidirectional"))
    )
    (net (code "13") (name "/GPIO0_4") (class "Default")
      (node (ref "D5") (pin "1") (pinfunction "A_1") (pintype "passive"))
      (node (ref "P2") (pin "9") (pinfunction "9_9") (pintype "passive"))
      (node (ref "U6") (pin "6") (pinfunction "IO,_VREFB1N0_6") (pintype "bidirectional"))
    )
    (net (code "14") (name "/GPIO0_5") (class "Default")
      (node (ref "D6") (pin "1") (pinfunction "A_1") (pintype "passive"))
      (node (ref "P2") (pin "10") (pinfunction "10_10") (pintype "passive"))
      (node (ref "U6") (pin "9") (pinfunction "IO,_(DQS2L/CQ3L,CDPCLK0)_9") (pintype "bidirectional"))
    )
    (net (code "15") (name "/GPIO0_6") (class "Default")
      (node (ref "P2") (pin "11") (pinfunction "11_11") (pintype "passive"))
    )
    (net (code "16") (name "/GPIO0_7") (class "Default")
      (node (ref "P2") (pin "12") (pinfunction "12_12") (pintype "passive"))
    )
    (net (code "17") (name "/GPIO0_8") (class "Default")
      (node (ref "P2") (pin "13") (pinfunction "13_13") (pintype "passive"))
      (node (ref "U6") (pin "240") (pinfunction "IO,_PLL3_CLKOUTp_240") (pintype "bidirectional"))
    )
    (net (code "18") (name "/GPIO0_9") (class "Default")
      (node (ref "P2") (pin "14") (pinfunction "14_14") (pintype "passive"))
      (node (ref "U6") (pin "239") (pinfunction "IO,_PLL3_CLKOUTn_239") (pintype "bidirectional"))
    )
    (net (code "19") (name "/GPIO0_10") (class "Default")
      (node (ref "P2") (pin "15") (pinfunction "15_15") (pintype "passive"))
      (node (ref "U6") (pin "236") (pinfunction "IO,_(DATA12),_(DQS1T/CQ1T#,CDPCLK7)_236") (pintype "bidirectional"))
    )
    (net (code "20") (name "/GPIO0_11") (class "Default")
      (node (ref "P2") (pin "16") (pinfunction "16_16") (pintype "passive"))
      (node (ref "U6") (pin "235") (pinfunction "IO,_VREFB8N3_235") (pintype "bidirectional"))
    )
    (net (code "21") (name "/GPIO0_12") (class "Default")
      (node (ref "P2") (pin "17") (pinfunction "17_17") (pintype "passive"))
      (node (ref "U6") (pin "232") (pinfunction "IO,_(DATA7),_(DM5T/BWS#5T)_232") (pintype "bidirectional"))
    )
    (net (code "22") (name "/GPIO0_13") (class "Default")
      (node (ref "P2") (pin "18") (pinfunction "18_18") (pintype "passive"))
      (node (ref "U6") (pin "231") (pinfunction "IO,_(DATA6),_(DQ5T)_231") (pintype "bidirectional"))
    )
    (net (code "23") (name "/GPIO0_14") (class "Default")
      (node (ref "P2") (pin "19") (pinfunction "19_19") (pintype "passive"))
      (node (ref "U6") (pin "230") (pinfunction "IO,_VREFB8N2_230") (pintype "bidirectional"))
    )
    (net (code "24") (name "/GPIO0_15") (class "Default")
      (node (ref "P2") (pin "20") (pinfunction "20_20") (pintype "passive"))
      (node (ref "U6") (pin "226") (pinfunction "IO,_(DATA5),_(DQ5T)_226") (pintype "bidirectional"))
    )
    (net (code "25") (name "/GPIO0_16") (class "Default")
      (node (ref "P2") (pin "21") (pinfunction "21_21") (pintype "passive"))
      (node (ref "U6") (pin "224") (pinfunction "IO,_(DATA14),_(DQS3T/CQ3T#,DPCLK11)_224") (pintype "bidirectional"))
    )
    (net (code "26") (name "/GPIO0_17") (class "Default")
      (node (ref "P2") (pin "22") (pinfunction "22_22") (pintype "passive"))
      (node (ref "U6") (pin "223") (pinfunction "IO,_VREFB8N1_223") (pintype "bidirectional"))
    )
    (net (code "27") (name "/GPIO0_18") (class "Default")
      (node (ref "P2") (pin "23") (pinfunction "23_23") (pintype "passive"))
      (node (ref "U6") (pin "221") (pinfunction "IO,_(DATA4),_(DQ5T)_221") (pintype "bidirectional"))
    )
    (net (code "28") (name "/GPIO0_19") (class "Default")
      (node (ref "P2") (pin "24") (pinfunction "24_24") (pintype "passive"))
      (node (ref "U6") (pin "219") (pinfunction "IO,_DIFFIO_T20p,_(DATA3),_(DQ5T)_219") (pintype "bidirectional"))
    )
    (net (code "29") (name "/GPIO0_20") (class "Default")
      (node (ref "P2") (pin "25") (pinfunction "25_25") (pintype "passive"))
      (node (ref "U6") (pin "218") (pinfunction "IO,_DIFFIO_T20n,_(DATA2)_218") (pintype "bidirectional"))
    )
    (net (code "30") (name "/GPIO0_21") (class "Default")
      (node (ref "P2") (pin "26") (pinfunction "26_26") (pintype "passive"))
      (node (ref "U6") (pin "217") (pinfunction "IO,_(DQ5T)_217") (pintype "bidirectional"))
    )
    (net (code "31") (name "/GPIO0_22") (class "Default")
      (node (ref "P2") (pin "27") (pinfunction "27_27") (pintype "passive"))
      (node (ref "U6") (pin "216") (pinfunction "IO,_VREFB8N0_216") (pintype "bidirectional"))
    )
    (net (code "32") (name "/GPIO0_23") (class "Default")
      (node (ref "P2") (pin "28") (pinfunction "28_28") (pintype "passive"))
      (node (ref "U6") (pin "214") (pinfunction "IO,_(PADD17),_(DQS5T/CQ5T#,DPCLK10)_214") (pintype "bidirectional"))
    )
    (net (code "33") (name "/GPIO0_24") (class "Default")
      (node (ref "P2") (pin "29") (pinfunction "29_29") (pintype "passive"))
      (node (ref "U6") (pin "207") (pinfunction "IO,_(PADD12),_(DQS4T/CQ5T,DPCLK9)_207") (pintype "bidirectional"))
    )
    (net (code "34") (name "/GPIO0_25") (class "Default")
      (node (ref "P2") (pin "30") (pinfunction "30_30") (pintype "passive"))
      (node (ref "U6") (pin "203") (pinfunction "IO,_VREFB7N3_203") (pintype "bidirectional"))
    )
    (net (code "35") (name "/GPIO0_26") (class "Default")
      (node (ref "P2") (pin "31") (pinfunction "31_31") (pintype "passive"))
      (node (ref "U6") (pin "202") (pinfunction "IO,_DIFFIO_T36p,_(PADD6),_(DQ5T)_202") (pintype "bidirectional"))
    )
    (net (code "36") (name "/GPIO0_27") (class "Default")
      (node (ref "P2") (pin "32") (pinfunction "32_32") (pintype "passive"))
      (node (ref "U6") (pin "201") (pinfunction "IO,_DIFFIO_T36n,_(PADD5),_(DQ5T)_201") (pintype "bidirectional"))
    )
    (net (code "37") (name "/GPIO0_28") (class "Default")
      (node (ref "P2") (pin "33") (pinfunction "33_33") (pintype "passive"))
      (node (ref "U6") (pin "200") (pinfunction "IO,_(PADD4),_(DQS2T/CQ3T,DPCLK8)_200") (pintype "bidirectional"))
    )
    (net (code "38") (name "/GPIO0_29") (class "Default")
      (node (ref "P2") (pin "34") (pinfunction "34_34") (pintype "passive"))
      (node (ref "U6") (pin "197") (pinfunction "IO,_DIFFIO_T38p,_(DQ5T)_197") (pintype "bidirectional"))
    )
    (net (code "39") (name "/GPIO0_30") (class "Default")
      (node (ref "P2") (pin "35") (pinfunction "35_35") (pintype "passive"))
      (node (ref "U6") (pin "196") (pinfunction "IO,_DIFFIO_T38n,_(PADD3)_196") (pintype "bidirectional"))
    )
    (net (code "40") (name "/GPIO0_31") (class "Default")
      (node (ref "P2") (pin "36") (pinfunction "36_36") (pintype "passive"))
      (node (ref "U6") (pin "195") (pinfunction "IO,_VREFB7N2_195") (pintype "bidirectional"))
    )
    (net (code "41") (name "/GPIO1_0") (class "Default")
      (node (ref "P3") (pin "5") (pinfunction "5_5") (pintype "passive"))
      (node (ref "U6") (pin "52") (pinfunction "IO,_RDN1,_(DQ1L)_52") (pintype "bidirectional"))
    )
    (net (code "42") (name "/GPIO1_1") (class "Default")
      (node (ref "P3") (pin "6") (pinfunction "6_6") (pintype "passive"))
      (node (ref "U6") (pin "55") (pinfunction "IO,_(DQS3L/CQ3L#,CDPCLK1)_55") (pintype "bidirectional"))
    )
    (net (code "43") (name "/GPIO1_2") (class "Default")
      (node (ref "P3") (pin "7") (pinfunction "7_7") (pintype "passive"))
      (node (ref "U6") (pin "56") (pinfunction "IO,_VREFB2N3_56") (pintype "bidirectional"))
    )
    (net (code "44") (name "/GPIO1_3") (class "Default")
      (node (ref "P3") (pin "8") (pinfunction "8_8") (pintype "passive"))
      (node (ref "U6") (pin "57") (pinfunction "IO,_(DQ1L)_57") (pintype "bidirectional"))
    )
    (net (code "45") (name "/GPIO1_4") (class "Default")
      (node (ref "P3") (pin "9") (pinfunction "9_9") (pintype "passive"))
      (node (ref "U6") (pin "63") (pinfunction "IO,_VREFB3N3_63") (pintype "bidirectional"))
    )
    (net (code "46") (name "/GPIO1_5") (class "Default")
      (node (ref "P3") (pin "10") (pinfunction "10_10") (pintype "passive"))
      (node (ref "U6") (pin "68") (pinfunction "IO,_(DQS1B/CQ1B#,CDPCLK2)_68") (pintype "bidirectional"))
    )
    (net (code "47") (name "/GPIO1_6") (class "Default")
      (node (ref "P3") (pin "11") (pinfunction "11_11") (pintype "passive"))
      (node (ref "U6") (pin "69") (pinfunction "IO,_PLL1_CLKOUTp_69") (pintype "bidirectional"))
    )
    (net (code "48") (name "/GPIO1_7") (class "Default")
      (node (ref "P3") (pin "12") (pinfunction "12_12") (pintype "passive"))
      (node (ref "U6") (pin "70") (pinfunction "IO,_PLL1_CLKOUTn_70") (pintype "bidirectional"))
    )
    (net (code "49") (name "/GPIO1_8") (class "Default")
      (node (ref "P3") (pin "13") (pinfunction "13_13") (pintype "passive"))
      (node (ref "U6") (pin "73") (pinfunction "IO,_VREFB3N2_73") (pintype "bidirectional"))
    )
    (net (code "50") (name "/GPIO1_9") (class "Default")
      (node (ref "P3") (pin "14") (pinfunction "14_14") (pintype "passive"))
      (node (ref "U6") (pin "76") (pinfunction "IO,_VREFB3N1_76") (pintype "bidirectional"))
    )
    (net (code "51") (name "/GPIO1_10") (class "Default")
      (node (ref "P3") (pin "15") (pinfunction "15_15") (pintype "passive"))
      (node (ref "U6") (pin "78") (pinfunction "IO,_(DQS3B/CQ3B#,DPCLK2)_78") (pintype "bidirectional"))
    )
    (net (code "52") (name "/GPIO1_11") (class "Default")
      (node (ref "P3") (pin "16") (pinfunction "16_16") (pintype "passive"))
      (node (ref "U6") (pin "80") (pinfunction "IO,_(DM5B/BWS#5B)_80") (pintype "bidirectional"))
    )
    (net (code "53") (name "/GPIO1_12") (class "Default")
      (node (ref "P3") (pin "17") (pinfunction "17_17") (pintype "passive"))
      (node (ref "U6") (pin "81") (pinfunction "IO,_DIFFIO_B18p,_(DQ5B)_81") (pintype "bidirectional"))
    )
    (net (code "54") (name "/GPIO1_13") (class "Default")
      (node (ref "P3") (pin "18") (pinfunction "18_18") (pintype "passive"))
      (node (ref "U6") (pin "82") (pinfunction "IO,_DIFFIO_B18n,_(DQ5B)_82") (pintype "bidirectional"))
    )
    (net (code "55") (name "/GPIO1_14") (class "Default")
      (node (ref "P3") (pin "19") (pinfunction "19_19") (pintype "passive"))
      (node (ref "U6") (pin "83") (pinfunction "IO,_(DQS5B/CQ5B#,DPCLK3)_83") (pintype "bidirectional"))
    )
    (net (code "56") (name "/GPIO1_15") (class "Default")
      (node (ref "P3") (pin "20") (pinfunction "20_20") (pintype "passive"))
      (node (ref "U6") (pin "84") (pinfunction "IO,_VREFB3N0_84") (pintype "bidirectional"))
    )
    (net (code "57") (name "/GPIO1_16") (class "Default")
      (node (ref "P3") (pin "21") (pinfunction "21_21") (pintype "passive"))
      (node (ref "U6") (pin "87") (pinfunction "IO,_DIFFIO_B27p,_(DQ5B)_87") (pintype "bidirectional"))
    )
    (net (code "58") (name "/GPIO1_17") (class "Default")
      (node (ref "P3") (pin "22") (pinfunction "22_22") (pintype "passive"))
      (node (ref "U6") (pin "88") (pinfunction "IO,_DIFFIO_B27n,_(DQ5B)_88") (pintype "bidirectional"))
    )
    (net (code "59") (name "/GPIO1_18") (class "Default")
      (node (ref "P3") (pin "23") (pinfunction "23_23") (pintype "passive"))
      (node (ref "U6") (pin "93") (pinfunction "IO,_DIFFIO_B28p,_(DQ5B)_93") (pintype "bidirectional"))
    )
    (net (code "60") (name "/GPIO1_19") (class "Default")
      (node (ref "P3") (pin "24") (pinfunction "24_24") (pintype "passive"))
      (node (ref "U6") (pin "94") (pinfunction "IO,_DIFFIO_B28n,_(DQ5B)_94") (pintype "bidirectional"))
    )
    (net (code "61") (name "/GPIO1_20") (class "Default")
      (node (ref "P3") (pin "25") (pinfunction "25_25") (pintype "passive"))
      (node (ref "U6") (pin "95") (pinfunction "IO,_VREFB4N3_95") (pintype "bidirectional"))
    )
    (net (code "62") (name "/GPIO1_21") (class "Default")
      (node (ref "P3") (pin "26") (pinfunction "26_26") (pintype "passive"))
      (node (ref "U6") (pin "98") (pinfunction "IO,_DIFFIO_B32p,_(DQ5B)_98") (pintype "bidirectional"))
    )
    (net (code "63") (name "/GPIO1_22") (class "Default")
      (node (ref "P3") (pin "27") (pinfunction "27_27") (pintype "passive"))
      (node (ref "U6") (pin "99") (pinfunction "IO,_DIFFIO_B32n,_(DQS4B/CQ5B,DPCLK4)_99") (pintype "bidirectional"))
    )
    (net (code "64") (name "/GPIO1_23") (class "Default")
      (node (ref "P3") (pin "28") (pinfunction "28_28") (pintype "passive"))
      (node (ref "U6") (pin "100") (pinfunction "IO,_(DQ5B)_100") (pintype "bidirectional"))
    )
    (net (code "65") (name "/GPIO1_24") (class "Default")
      (node (ref "P3") (pin "29") (pinfunction "29_29") (pintype "passive"))
      (node (ref "U6") (pin "103") (pinfunction "IO,_(DQ5B)_103") (pintype "bidirectional"))
    )
    (net (code "66") (name "/GPIO1_25") (class "Default")
      (node (ref "P3") (pin "30") (pinfunction "30_30") (pintype "passive"))
      (node (ref "U6") (pin "106") (pinfunction "IO,_(DQS2B/CQ3B,DPCLK5)_106") (pintype "bidirectional"))
    )
    (net (code "67") (name "/GPIO1_26") (class "Default")
      (node (ref "P3") (pin "31") (pinfunction "31_31") (pintype "passive"))
      (node (ref "U6") (pin "107") (pinfunction "IO,_VREFB4N2_107") (pintype "bidirectional"))
    )
    (net (code "68") (name "/GPIO1_27") (class "Default")
      (node (ref "P3") (pin "32") (pinfunction "32_32") (pintype "passive"))
      (node (ref "U6") (pin "110") (pinfunction "IO,_VREFB4N1_110") (pintype "bidirectional"))
    )
    (net (code "69") (name "/GPIO1_28") (class "Default")
      (node (ref "P3") (pin "33") (pinfunction "33_33") (pintype "passive"))
      (node (ref "U6") (pin "111") (pinfunction "IO,_RUP2_111") (pintype "bidirectional"))
    )
    (net (code "70") (name "/HyperBUS_CK") (class "Default")
      (node (ref "U6") (pin "38") (pinfunction "IO,_DIFFIO_L28n,_(DQ1L)_38") (pintype "bidirectional"))
      (node (ref "U7") (pin "B2") (pinfunction "CK_B2") (pintype "input"))
    )
    (net (code "71") (name "/HyperBUS_DQ0") (class "Default")
      (node (ref "U6") (pin "46") (pinfunction "IO,_VREFB2N1_46") (pintype "bidirectional"))
      (node (ref "U7") (pin "D3") (pinfunction "DQ0_D3") (pintype "bidirectional"))
    )
    (net (code "72") (name "/HyperBUS_DQ1") (class "Default")
      (node (ref "U6") (pin "43") (pinfunction "IO,_(DQ1L)_43") (pintype "bidirectional"))
      (node (ref "U7") (pin "D2") (pinfunction "DQ1_D2") (pintype "bidirectional"))
    )
    (net (code "73") (name "/HyperBUS_DQ2") (class "Default")
      (node (ref "U6") (pin "41") (pinfunction "IO,_(DQ1L)_41") (pintype "bidirectional"))
      (node (ref "U7") (pin "C4") (pinfunction "DQ2_C4") (pintype "bidirectional"))
    )
    (net (code "74") (name "/HyperBUS_DQ3") (class "Default")
      (node (ref "U6") (pin "44") (pinfunction "IO,_DIFFIO_L34p,_(DQS1L/CQ1L#,DPCLK1)_44") (pintype "bidirectional"))
      (node (ref "U7") (pin "D4") (pinfunction "DQ3_D4") (pintype "bidirectional"))
    )
    (net (code "75") (name "/HyperBUS_DQ4") (class "Default")
      (node (ref "U6") (pin "45") (pinfunction "IO,_DIFFIO_L34n,_(DQ1L)_45") (pintype "bidirectional"))
      (node (ref "U7") (pin "D5") (pinfunction "DQ4_D5") (pintype "bidirectional"))
    )
    (net (code "76") (name "/HyperBUS_DQ5") (class "Default")
      (node (ref "U6") (pin "49") (pinfunction "IO,_(DQ1L)_49") (pintype "bidirectional"))
      (node (ref "U7") (pin "E3") (pinfunction "DQ5_E3") (pintype "bidirectional"))
    )
    (net (code "77") (name "/HyperBUS_DQ6") (class "Default")
      (node (ref "U6") (pin "50") (pinfunction "IO,_VREFB2N2_50") (pintype "bidirectional"))
      (node (ref "U7") (pin "E2") (pinfunction "DQ6_E2") (pintype "bidirectional"))
    )
    (net (code "78") (name "/HyperBUS_DQ7") (class "Default")
      (node (ref "U6") (pin "51") (pinfunction "IO,_RUP1,_(DQ1L)_51") (pintype "bidirectional"))
      (node (ref "U7") (pin "E1") (pinfunction "DQ7_E1") (pintype "bidirectional"))
    )
    (net (code "79") (name "/HyperBUS_RWDS") (class "Default")
      (node (ref "U6") (pin "39") (pinfunction "IO,_VREFB2N0_39") (pintype "bidirectional"))
      (node (ref "U7") (pin "C3") (pinfunction "RWDS_C3") (pintype "bidirectional"))
    )
    (net (code "80") (name "/HyperBUS_nCS") (class "Default")
      (node (ref "U6") (pin "37") (pinfunction "IO,_DIFFIO_L28p,_(DQ1L)_37") (pintype "bidirectional"))
      (node (ref "U7") (pin "A3") (pinfunction "CS#_A3") (pintype "input"))
    )
    (net (code "81") (name "/HyperBUS_nRESET") (class "Default")
      (node (ref "R13") (pin "1") (pinfunction "1_1") (pintype "passive"))
      (node (ref "U7") (pin "A4") (pinfunction "RESET#_A4") (pintype "input"))
    )
    (net (code "82") (name "/JTAG_TCK") (class "Default")
      (node (ref "J3") (pin "1") (pinfunction "1_1") (pintype "passive"))
      (node (ref "R17") (pin "1") (pinfunction "1_1") (pintype "passive"))
    )
    (net (code "83") (name "/JTAG_TDI") (class "Default")
      (node (ref "J3") (pin "9") (pinfunction "9_9") (pintype "passive"))
      (node (ref "R16") (pin "1") (pinfunction "1_1") (pintype "passive"))
    )
    (net (code "84") (name "/JTAG_TDO") (class "Default")
      (node (ref "J3") (pin "3") (pinfunction "3_3") (pintype "passive"))
      (node (ref "U6") (pin "29") (pinfunction "TDO_29") (pintype "output"))
    )
    (net (code "85") (name "/JTAG_TMS") (class "Default")
      (node (ref "J3") (pin "5") (pinfunction "5_5") (pintype "passive"))
      (node (ref "U6") (pin "28") (pinfunction "TMS_28") (pintype "input"))
    )
    (net (code "86") (name "/MSEL0") (class "Default")
      (node (ref "R18") (pin "1") (pinfunction "1_1") (pintype "passive"))
      (node (ref "R21") (pin "2") (pinfunction "2_2") (pintype "passive"))
      (node (ref "U6") (pin "155") (pinfunction "MSEL0_155") (pintype "input"))
    )
    (net (code "87") (name "/MSEL1") (class "Default")
      (node (ref "R19") (pin "1") (pinfunction "1_1") (pintype "passive"))
      (node (ref "R22") (pin "2") (pinfunction "2_2") (pintype "passive"))
      (node (ref "U6") (pin "157") (pinfunction "MSEL1_157") (pintype "input"))
    )
    (net (code "88") (name "/MSEL2") (class "Default")
      (node (ref "R20") (pin "1") (pinfunction "1_1") (pintype "passive"))
      (node (ref "R23") (pin "2") (pinfunction "2_2") (pintype "passive"))
      (node (ref "U6") (pin "158") (pinfunction "MSEL2_158") (pintype "input"))
    )
    (net (code "89") (name "/SDRAM_A0") (class "Default")
      (node (ref "U6") (pin "139") (pinfunction "IO,_VREFB5N2_139") (pintype "bidirectional"))
      (node (ref "U9") (pin "23") (pinfunction "A0_23") (pintype "input"))
    )
    (net (code "90") (name "/SDRAM_A1") (class "Default")
      (node (ref "U6") (pin "137") (pinfunction "IO,_(DQ1R)_137") (pintype "bidirectional"))
      (node (ref "U9") (pin "24") (pinfunction "A1_24") (pintype "input"))
    )
    (net (code "91") (name "/SDRAM_A2") (class "Default")
      (node (ref "U6") (pin "135") (pinfunction "IO,_DIFFIO_R51p,_(DQ1R)_135") (pintype "bidirectional"))
      (node (ref "U9") (pin "25") (pinfunction "A2_25") (pintype "input"))
    )
    (net (code "92") (name "/SDRAM_A3") (class "Default")
      (node (ref "U6") (pin "134") (pinfunction "IO,_DIFFIO_R51n,_(DQ1R)_134") (pintype "bidirectional"))
      (node (ref "U9") (pin "26") (pinfunction "A3_26") (pintype "input"))
    )
    (net (code "93") (name "/SDRAM_A4") (class "Default")
      (node (ref "U6") (pin "112") (pinfunction "IO,_RDN2_112") (pintype "bidirectional"))
      (node (ref "U9") (pin "29") (pinfunction "A4_29") (pintype "input"))
    )
    (net (code "94") (name "/SDRAM_A5") (class "Default")
      (node (ref "U6") (pin "113") (pinfunction "IO,_(DQS0B/CQ1B,CDPCLK3)_113") (pintype "bidirectional"))
      (node (ref "U9") (pin "30") (pinfunction "A5_30") (pintype "input"))
    )
    (net (code "95") (name "/SDRAM_A6") (class "Default")
      (node (ref "U6") (pin "114") (pinfunction "IO,_VREFB4N0_114") (pintype "bidirectional"))
      (node (ref "U9") (pin "31") (pinfunction "A6_31") (pintype "input"))
    )
    (net (code "96") (name "/SDRAM_A7") (class "Default")
      (node (ref "U6") (pin "117") (pinfunction "IO,_PLL4_CLKOUTp_117") (pintype "bidirectional"))
      (node (ref "U9") (pin "32") (pinfunction "A7_32") (pintype "input"))
    )
    (net (code "97") (name "/SDRAM_A8") (class "Default")
      (node (ref "U6") (pin "118") (pinfunction "IO,_PLL4_CLKOUTn_118") (pintype "bidirectional"))
      (node (ref "U9") (pin "33") (pinfunction "A8_33") (pintype "input"))
    )
    (net (code "98") (name "/SDRAM_A9") (class "Default")
      (node (ref "U6") (pin "126") (pinfunction "IO,_RUP3,_(DQ1R)_126") (pintype "bidirectional"))
      (node (ref "U9") (pin "34") (pinfunction "A9_34") (pintype "input"))
    )
    (net (code "99") (name "/SDRAM_A10") (class "Default")
      (node (ref "U6") (pin "142") (pinfunction "IO,_VREFB5N1_142") (pintype "bidirectional"))
      (node (ref "U9") (pin "22") (pinfunction "A10_22") (pintype "input"))
    )
    (net (code "100") (name "/SDRAM_A11") (class "Default")
      (node (ref "U6") (pin "127") (pinfunction "IO,_RDN3,_(DQ1R)_127") (pintype "bidirectional"))
      (node (ref "U9") (pin "35") (pinfunction "A11_35") (pintype "input"))
    )
    (net (code "101") (name "/SDRAM_A12") (class "Default")
      (node (ref "U6") (pin "128") (pinfunction "IO,_(DQS3R/CQ3R#,CDPCLK4)_128") (pintype "bidirectional"))
      (node (ref "U9") (pin "36") (pinfunction "A12_36") (pintype "input"))
    )
    (net (code "102") (name "/SDRAM_BA0") (class "Default")
      (node (ref "U6") (pin "144") (pinfunction "IO,_DIFFIO_R32n,_(DEV_OE)_144") (pintype "bidirectional"))
      (node (ref "U9") (pin "20") (pinfunction "BA0_20") (pintype "input"))
    )
    (net (code "103") (name "/SDRAM_BA1") (class "Default")
      (node (ref "U6") (pin "143") (pinfunction "IO,_(DQS1R/CQ1R#,DPCLK6)_143") (pintype "bidirectional"))
      (node (ref "U9") (pin "21") (pinfunction "BA1_21") (pintype "input"))
    )
    (net (code "104") (name "/SDRAM_CKE") (class "Default")
      (node (ref "U6") (pin "131") (pinfunction "IO,_DIFFIO_R53n,_(DQ1R)_131") (pintype "bidirectional"))
      (node (ref "U9") (pin "37") (pinfunction "CKE_37") (pintype "input"))
    )
    (net (code "105") (name "/SDRAM_CLK") (class "Default")
      (node (ref "U6") (pin "132") (pinfunction "IO,_DIFFIO_R53p,_(DQ1R)_132") (pintype "bidirectional"))
      (node (ref "U9") (pin "38") (pinfunction "CLK_38") (pintype "input"))
    )
    (net (code "106") (name "/SDRAM_DQ0") (class "Default")
      (node (ref "U6") (pin "177") (pinfunction "IO,_VREFB6N0_177") (pintype "bidirectional"))
      (node (ref "U9") (pin "2") (pinfunction "DQ0_2") (pintype "bidirectional"))
    )
    (net (code "107") (name "/SDRAM_DQ1") (class "Default")
      (node (ref "U6") (pin "176") (pinfunction "IO,_(PADD20),_(DQS2R/CQ3R,CDPCLK5)_176") (pintype "bidirectional"))
      (node (ref "U9") (pin "4") (pinfunction "DQ1_4") (pintype "bidirectional"))
    )
    (net (code "108") (name "/SDRAM_DQ2") (class "Default")
      (node (ref "U6") (pin "173") (pinfunction "IO,_VREFB6N1_173") (pintype "bidirectional"))
      (node (ref "U9") (pin "5") (pinfunction "DQ2_5") (pintype "bidirectional"))
    )
    (net (code "109") (name "/SDRAM_DQ3") (class "Default")
      (node (ref "U6") (pin "171") (pinfunction "IO,_(nWE),_(DQ1R)_171") (pintype "bidirectional"))
      (node (ref "U9") (pin "7") (pinfunction "DQ3_7") (pintype "bidirectional"))
    )
    (net (code "110") (name "/SDRAM_DQ4") (class "Default")
      (node (ref "U6") (pin "169") (pinfunction "IO,_VREFB6N2_169") (pintype "bidirectional"))
      (node (ref "U9") (pin "8") (pinfunction "DQ4_8") (pintype "bidirectional"))
    )
    (net (code "111") (name "/SDRAM_DQ5") (class "Default")
      (node (ref "U6") (pin "166") (pinfunction "IO,_(DQS0R/CQ1R,DPCLK7)_166") (pintype "bidirectional"))
      (node (ref "U9") (pin "10") (pinfunction "DQ5_10") (pintype "bidirectional"))
    )
    (net (code "112") (name "/SDRAM_DQ6") (class "Default")
      (node (ref "U6") (pin "164") (pinfunction "IO,_DIFFIO_R24p,_(CLKUSR)_164") (pintype "bidirectional"))
      (node (ref "U9") (pin "11") (pinfunction "DQ6_11") (pintype "bidirectional"))
    )
    (net (code "113") (name "/SDRAM_DQ7") (class "Default")
      (node (ref "U6") (pin "162") (pinfunction "IO,_DIFFIO_R24n,_(nCEO)_162") (pintype "bidirectional"))
      (node (ref "U9") (pin "13") (pinfunction "DQ7_13") (pintype "bidirectional"))
    )
    (net (code "114") (name "/SDRAM_DQ8") (class "Default")
      (node (ref "U6") (pin "183") (pinfunction "IO,_(DQS0T/CQ1T,CDPCLK6)_183") (pintype "bidirectional"))
      (node (ref "U9") (pin "42") (pinfunction "DQ8_42") (pintype "bidirectional"))
    )
    (net (code "115") (name "/SDRAM_DQ9") (class "Default")
      (node (ref "U6") (pin "184") (pinfunction "IO,_VREFB7N0_184") (pintype "bidirectional"))
      (node (ref "U9") (pin "44") (pinfunction "DQ9_44") (pintype "bidirectional"))
    )
    (net (code "116") (name "/SDRAM_DQ10") (class "Default")
      (node (ref "U6") (pin "185") (pinfunction "IO,_PLL2_CLKOUTn_185") (pintype "bidirectional"))
      (node (ref "U9") (pin "45") (pinfunction "DQ10_45") (pintype "bidirectional"))
    )
    (net (code "117") (name "/SDRAM_DQ11") (class "Default")
      (node (ref "U6") (pin "186") (pinfunction "IO,_PLL2_CLKOUTp_186") (pintype "bidirectional"))
      (node (ref "U9") (pin "47") (pinfunction "DQ11_47") (pintype "bidirectional"))
    )
    (net (code "118") (name "/SDRAM_DQ12") (class "Default")
      (node (ref "U6") (pin "187") (pinfunction "IO,_RUP4_187") (pintype "bidirectional"))
      (node (ref "U9") (pin "48") (pinfunction "DQ12_48") (pintype "bidirectional"))
    )
    (net (code "119") (name "/SDRAM_DQ13") (class "Default")
      (node (ref "U6") (pin "188") (pinfunction "IO,_RDN4_188") (pintype "bidirectional"))
      (node (ref "U9") (pin "50") (pinfunction "DQ13_50") (pintype "bidirectional"))
    )
    (net (code "120") (name "/SDRAM_DQ14") (class "Default")
      (node (ref "U6") (pin "189") (pinfunction "IO,_VREFB7N1_189") (pintype "bidirectional"))
      (node (ref "U9") (pin "51") (pinfunction "DQ14_51") (pintype "bidirectional"))
    )
    (net (code "121") (name "/SDRAM_DQ15") (class "Default")
      (node (ref "U6") (pin "194") (pinfunction "IO,_(PADD2),_(DQ5T)_194") (pintype "bidirectional"))
      (node (ref "U9") (pin "53") (pinfunction "DQ15_53") (pintype "bidirectional"))
    )
    (net (code "122") (name "/SDRAM_DQM0") (class "Default")
      (node (ref "U6") (pin "161") (pinfunction "IO,_VREFB6N3_161") (pintype "bidirectional"))
      (node (ref "U9") (pin "15") (pinfunction "DQML_15") (pintype "input"))
    )
    (net (code "123") (name "/SDRAM_DQM1") (class "Default")
      (node (ref "U6") (pin "133") (pinfunction "IO,_VREFB5N3_133") (pintype "bidirectional"))
      (node (ref "U9") (pin "39") (pinfunction "DQMH_39") (pintype "input"))
    )
    (net (code "124") (name "/SDRAM_nCAS") (class "Default")
      (node (ref "U6") (pin "159") (pinfunction "IO,_DIFFIO_R27n,_(INIT_DONE)_159") (pintype "bidirectional"))
      (node (ref "U9") (pin "17") (pinfunction "CAS#_17") (pintype "input"))
    )
    (net (code "125") (name "/SDRAM_nCS") (class "Default")
      (node (ref "U6") (pin "145") (pinfunction "IO,_DIFFIO_R32p,_(DEV_CLRn)_145") (pintype "bidirectional"))
      (node (ref "U9") (pin "19") (pinfunction "CS#_19") (pintype "input"))
    )
    (net (code "126") (name "/SDRAM_nRAS") (class "Default")
      (node (ref "U6") (pin "146") (pinfunction "IO,_VREFB5N0_146") (pintype "bidirectional"))
      (node (ref "U9") (pin "18") (pinfunction "RAS#_18") (pintype "input"))
    )
    (net (code "127") (name "/SDRAM_nWE") (class "Default")
      (node (ref "U6") (pin "160") (pinfunction "IO,_DIFFIO_R27p,_(CRC_ERROR)_160") (pintype "bidirectional"))
      (node (ref "U9") (pin "16") (pinfunction "WE#_16") (pintype "input"))
    )
    (net (code "128") (name "/nCE") (class "Default")
      (node (ref "J2") (pin "6") (pinfunction "6_6") (pintype "passive"))
      (node (ref "R24") (pin "1") (pinfunction "1_1") (pintype "passive"))
      (node (ref "U6") (pin "30") (pinfunction "nCE_30") (pintype "input"))
    )
    (net (code "129") (name "/nCONFIG") (class "Default")
      (node (ref "J2") (pin "5") (pinfunction "5_5") (pintype "passive"))
      (node (ref "R25") (pin "2") (pinfunction "2_2") (pintype "passive"))
      (node (ref "U6") (pin "25") (pinfunction "nCONFIG_25") (pintype "input"))
    )
    (net (code "130") (name "/nCSO") (class "Default")
      (node (ref "C16") (pin "1") (pinfunction "1_1") (pintype "passive"))
      (node (ref "D2") (pin "3") (pintype "passive"))
      (node (ref "J2") (pin "8") (pinfunction "8_8") (pintype "passive"))
      (node (ref "U6") (pin "14") (pinfunction "IO,_(FLASH_nCE,_nCSO)_14") (pintype "bidirectional"))
      (node (ref "U8") (pin "1") (pinfunction "S#_1") (pintype "input"))
    )
    (net (code "131") (name "/nSTATUS") (class "Default")
      (node (ref "R26") (pin "2") (pinfunction "2_2") (pintype "passive"))
      (node (ref "U6") (pin "17") (pinfunction "nSTATUS_17") (pintype "bidirectional"))
    )
    (net (code "132") (name "1.2V") (class "Default")
      (node (ref "C10") (pin "1") (pinfunction "1_1") (pintype "passive"))
      (node (ref "C41") (pin "2") (pinfunction "2_2") (pintype "passive"))
      (node (ref "C42") (pin "2") (pinfunction "2_2") (pintype "passive"))
      (node (ref "C43") (pin "2") (pinfunction "2_2") (pintype "passive"))
      (node (ref "C44") (pin "2") (pinfunction "2_2") (pintype "passive"))
      (node (ref "C45") (pin "2") (pinfunction "2_2") (pintype "passive"))
      (node (ref "C46") (pin "2") (pinfunction "2_2") (pintype "passive"))
      (node (ref "C47") (pin "2") (pinfunction "2_2") (pintype "passive"))
      (node (ref "C48") (pin "2") (pinfunction "2_2") (pintype "passive"))
      (node (ref "C49") (pin "2") (pinfunction "2_2") (pintype "passive"))
      (node (ref "C50") (pin "2") (pinfunction "2_2") (pintype "passive"))
      (node (ref "C51") (pin "2") (pinfunction "2_2") (pintype "passive"))
      (node (ref "C52") (pin "2") (pinfunction "2_2") (pintype "passive"))
      (node (ref "C53") (pin "2") (pinfunction "2_2") (pintype "passive"))
      (node (ref "C54") (pin "2") (pinfunction "2_2") (pintype "passive"))
      (node (ref "C55") (pin "2") (pinfunction "2_2") (pintype "passive"))
      (node (ref "C56") (pin "2") (pinfunction "2_2") (pintype "passive"))
      (node (ref "C57") (pin "2") (pinfunction "2_2") (pintype "passive"))
      (node (ref "C58") (pin "2") (pinfunction "2_2") (pintype "passive"))
      (node (ref "C59") (pin "2") (pinfunction "2_2") (pintype "passive"))
      (node (ref "C60") (pin "2") (pinfunction "2_2") (pintype "passive"))
      (node (ref "C61") (pin "2") (pinfunction "2_2") (pintype "passive"))
      (node (ref "C62") (pin "2") (pinfunction "2_2") (pintype "passive"))
      (node (ref "C63") (pin "2") (pinfunction "2_2") (pintype "passive"))
      (node (ref "C64") (pin "2") (pinfunction "2_2") (pintype "passive"))
      (node (ref "C65") (pin "2") (pinfunction "2_2") (pintype "passive"))
      (node (ref "C66") (pin "2") (pinfunction "2_2") (pintype "passive"))
      (node (ref "C67") (pin "2") (pinfunction "2_2") (pintype "passive"))
      (node (ref "C72") (pin "2") (pinfunction "2_2") (pintype "passive"))
      (node (ref "C73") (pin "2") (pinfunction "2_2") (pintype "passive"))
      (node (ref "C74") (pin "2") (pinfunction "2_2") (pintype "passive"))
      (node (ref "C75") (pin "2") (pinfunction "2_2") (pintype "passive"))
      (node (ref "L2") (pin "2") (pinfunction "2_2") (pintype "passive"))
      (node (ref "P1") (pin "1") (pinfunction "1_1") (pintype "passive"))
      (node (ref "R5") (pin "1") (pinfunction "1_1") (pintype "passive"))
      (node (ref "U4") (pin "2") (pinfunction "Vout_2") (pintype "passive"))
      (node (ref "U6") (pin "1") (pinfunction "VCCD_PLL3_1") (pintype "power_in"))
      (node (ref "U6") (pin "10") (pinfunction "VCCINT_10") (pintype "power_in"))
      (node (ref "U6") (pin "101") (pinfunction "VCCINT_101") (pintype "power_in"))
      (node (ref "U6") (pin "108") (pinfunction "VCCINT_108") (pintype "power_in"))
      (node (ref "U6") (pin "115") (pinfunction "VCCINT_115") (pintype "power_in"))
      (node (ref "U6") (pin "119") (pinfunction "VCCINT_119") (pintype "power_in"))
      (node (ref "U6") (pin "121") (pinfunction "VCCD_PLL4_121") (pintype "power_in"))
      (node (ref "U6") (pin "129") (pinfunction "VCCINT_129") (pintype "power_in"))
      (node (ref "U6") (pin "140") (pinfunction "VCCINT_140") (pintype "power_in"))
      (node (ref "U6") (pin "147") (pinfunction "VCCINT_147") (pintype "power_in"))
      (node (ref "U6") (pin "163") (pinfunction "VCCINT_163") (pintype "power_in"))
      (node (ref "U6") (pin "167") (pinfunction "VCCINT_167") (pintype "power_in"))
      (node (ref "U6") (pin "174") (pinfunction "VCCINT_174") (pintype "power_in"))
      (node (ref "U6") (pin "180") (pinfunction "VCCD_PLL2_180") (pintype "power_in"))
      (node (ref "U6") (pin "181") (pinfunction "VCCINT_181") (pintype "power_in"))
      (node (ref "U6") (pin "19") (pinfunction "VCCINT_19") (pintype "power_in"))
      (node (ref "U6") (pin "190") (pinfunction "VCCINT_190") (pintype "power_in"))
      (node (ref "U6") (pin "198") (pinfunction "VCCINT_198") (pintype "power_in"))
      (node (ref "U6") (pin "204") (pinfunction "VCCINT_204") (pintype "power_in"))
      (node (ref "U6") (pin "220") (pinfunction "VCCINT_220") (pintype "power_in"))
      (node (ref "U6") (pin "228") (pinfunction "VCCINT_228") (pintype "power_in"))
      (node (ref "U6") (pin "233") (pinfunction "VCCINT_233") (pintype "power_in"))
      (node (ref "U6") (pin "237") (pinfunction "VCCINT_237") (pintype "power_in"))
      (node (ref "U6") (pin "4") (pinfunction "VCCINT_4") (pintype "power_in"))
      (node (ref "U6") (pin "40") (pinfunction "VCCINT_40") (pintype "power_in"))
      (node (ref "U6") (pin "53") (pinfunction "VCCINT_53") (pintype "power_in"))
      (node (ref "U6") (pin "60") (pinfunction "VCCD_PLL1_60") (pintype "power_in"))
      (node (ref "U6") (pin "61") (pinfunction "VCCINT_61") (pintype "power_in"))
      (node (ref "U6") (pin "64") (pinfunction "VCCINT_64") (pintype "power_in"))
      (node (ref "U6") (pin "71") (pinfunction "VCCINT_71") (pintype "power_in"))
      (node (ref "U6") (pin "74") (pinfunction "VCCINT_74") (pintype "power_in"))
      (node (ref "U6") (pin "85") (pinfunction "VCCINT_85") (pintype "power_in"))
    )
    (net (code "133") (name "2.5V") (class "Default")
      (node (ref "C68") (pin "2") (pinfunction "2_2") (pintype "passive"))
      (node (ref "C69") (pin "2") (pinfunction "2_2") (pintype "passive"))
      (node (ref "C70") (pin "2") (pinfunction "2_2") (pintype "passive"))
      (node (ref "C71") (pin "2") (pinfunction "2_2") (pintype "passive"))
      (node (ref "C9") (pin "1") (pinfunction "1_1") (pintype "passive"))
      (node (ref "P1") (pin "3") (pinfunction "3_3") (pintype "passive"))
      (node (ref "R1") (pin "2") (pinfunction "2_2") (pintype "passive"))
      (node (ref "R18") (pin "2") (pinfunction "2_2") (pintype "passive"))
      (node (ref "R19") (pin "2") (pinfunction "2_2") (pintype "passive"))
      (node (ref "R20") (pin "2") (pinfunction "2_2") (pintype "passive"))
      (node (ref "U3") (pin "2") (pinfunction "Vout_2") (pintype "passive"))
      (node (ref "U4") (pin "3") (pinfunction "Vin_3") (pintype "passive"))
      (node (ref "U6") (pin "123") (pinfunction "VCCA4_123") (pintype "power_in"))
      (node (ref "U6") (pin "178") (pinfunction "VCCA2_178") (pintype "power_in"))
      (node (ref "U6") (pin "3") (pinfunction "VCCA3_3") (pintype "power_in"))
      (node (ref "U6") (pin "58") (pinfunction "VCCA1_58") (pintype "power_in"))
    )
    (net (code "134") (name "3.3V") (class "Default")
      (node (ref "C11") (pin "2") (pinfunction "2_2") (pintype "passive"))
      (node (ref "C12") (pin "2") (pinfunction "2_2") (pintype "passive"))
      (node (ref "C13") (pin "2") (pinfunction "2_2") (pintype "passive"))
      (node (ref "C14") (pin "2") (pinfunction "2_2") (pintype "passive"))
      (node (ref "C19") (pin "2") (pinfunction "2_2") (pintype "passive"))
      (node (ref "C20") (pin "2") (pinfunction "2_2") (pintype "passive"))
      (node (ref "C21") (pin "2") (pinfunction "2_2") (pintype "passive"))
      (node (ref "C22") (pin "2") (pinfunction "2_2") (pintype "passive"))
      (node (ref "C23") (pin "2") (pinfunction "2_2") (pintype "passive"))
      (node (ref "C24") (pin "2") (pinfunction "2_2") (pintype "passive"))
      (node (ref "C25") (pin "2") (pinfunction "2_2") (pintype "passive"))
      (node (ref "C26") (pin "2") (pinfunction "2_2") (pintype "passive"))
      (node (ref "C27") (pin "2") (pinfunction "2_2") (pintype "passive"))
      (node (ref "C28") (pin "2") (pinfunction "2_2") (pintype "passive"))
      (node (ref "C29") (pin "2") (pinfunction "2_2") (pintype "passive"))
      (node (ref "C30") (pin "2") (pinfunction "2_2") (pintype "passive"))
      (node (ref "C31") (pin "2") (pinfunction "2_2") (pintype "passive"))
      (node (ref "C32") (pin "2") (pinfunction "2_2") (pintype "passive"))
      (node (ref "C33") (pin "2") (pinfunction "2_2") (pintype "passive"))
      (node (ref "C34") (pin "2") (pinfunction "2_2") (pintype "passive"))
      (node (ref "C35") (pin "2") (pinfunction "2_2") (pintype "passive"))
      (node (ref "C36") (pin "2") (pinfunction "2_2") (pintype "passive"))
      (node (ref "C37") (pin "2") (pinfunction "2_2") (pintype "passive"))
      (node (ref "C38") (pin "2") (pinfunction "2_2") (pintype "passive"))
      (node (ref "C39") (pin "2") (pinfunction "2_2") (pintype "passive"))
      (node (ref "C40") (pin "2") (pinfunction "2_2") (pintype "passive"))
      (node (ref "C8") (pin "1") (pinfunction "1_1") (pintype "passive"))
      (node (ref "D1") (pin "2") (pintype "passive"))
      (node (ref "D2") (pin "2") (pintype "passive"))
      (node (ref "D3") (pin "2") (pintype "passive"))
      (node (ref "D4") (pin "2") (pintype "passive"))
      (node (ref "J2") (pin "4") (pinfunction "4_4") (pintype "passive"))
      (node (ref "J3") (pin "4") (pinfunction "4_4") (pintype "passive"))
      (node (ref "L1") (pin "2") (pinfunction "2_2") (pintype "passive"))
      (node (ref "P1") (pin "5") (pinfunction "5_5") (pintype "passive"))
      (node (ref "P2") (pin "1") (pinfunction "1_1") (pintype "passive"))
      (node (ref "P2") (pin "2") (pinfunction "2_2") (pintype "passive"))
      (node (ref "P2") (pin "39") (pinfunction "39_39") (pintype "passive"))
      (node (ref "P2") (pin "40") (pinfunction "40_40") (pintype "passive"))
      (node (ref "P3") (pin "1") (pinfunction "1_1") (pintype "passive"))
      (node (ref "P3") (pin "2") (pinfunction "2_2") (pintype "passive"))
      (node (ref "P3") (pin "39") (pinfunction "39_39") (pintype "passive"))
      (node (ref "P3") (pin "40") (pinfunction "40_40") (pintype "passive"))
      (node (ref "R11") (pin "2") (pinfunction "2_2") (pintype "passive"))
      (node (ref "R13") (pin "2") (pinfunction "2_2") (pintype "passive"))
      (node (ref "R14") (pin "2") (pinfunction "2_2") (pintype "passive"))
      (node (ref "R25") (pin "1") (pinfunction "1_1") (pintype "passive"))
      (node (ref "R26") (pin "1") (pinfunction "1_1") (pintype "passive"))
      (node (ref "R27") (pin "1") (pinfunction "1_1") (pintype "passive"))
      (node (ref "R4") (pin "1") (pinfunction "1_1") (pintype "passive"))
      (node (ref "U3") (pin "3") (pinfunction "Vin_3") (pintype "passive"))
      (node (ref "U5") (pin "2") (pinfunction "VOUT_2") (pintype "power_in"))
      (node (ref "U6") (pin "104") (pinfunction "VCCIO4_104") (pintype "power_in"))
      (node (ref "U6") (pin "124") (pinfunction "VCCIO5_124") (pintype "power_in"))
      (node (ref "U6") (pin "136") (pinfunction "VCCIO5_136") (pintype "power_in"))
      (node (ref "U6") (pin "15") (pinfunction "VCCIO1_15") (pintype "power_in"))
      (node (ref "U6") (pin "154") (pinfunction "VCCIO6_154") (pintype "power_in"))
      (node (ref "U6") (pin "170") (pinfunction "VCCIO6_170") (pintype "power_in"))
      (node (ref "U6") (pin "192") (pinfunction "VCCIO7_192") (pintype "power_in"))
      (node (ref "U6") (pin "206") (pinfunction "VCCIO7_206") (pintype "power_in"))
      (node (ref "U6") (pin "213") (pinfunction "VCCIO8_213") (pintype "power_in"))
      (node (ref "U6") (pin "225") (pinfunction "VCCIO8_225") (pintype "power_in"))
      (node (ref "U6") (pin "35") (pinfunction "VCCIO2_35") (pintype "power_in"))
      (node (ref "U6") (pin "47") (pinfunction "VCCIO2_47") (pintype "power_in"))
      (node (ref "U6") (pin "66") (pinfunction "VCCIO3_66") (pintype "power_in"))
      (node (ref "U6") (pin "7") (pinfunction "VCCIO1_7") (pintype "power_in"))
      (node (ref "U6") (pin "77") (pinfunction "VCCIO3_77") (pintype "power_in"))
      (node (ref "U6") (pin "96") (pinfunction "VCCIO4_96") (pintype "power_in"))
      (node (ref "U7") (pin "B4") (pinfunction "VCC_B4") (pintype "power_in"))
      (node (ref "U7") (pin "D1") (pinfunction "VCCQ_D1") (pintype "power_in"))
      (node (ref "U7") (pin "E4") (pinfunction "VCCQ_E4") (pintype "power_in"))
      (node (ref "U8") (pin "8") (pinfunction "VCC_8") (pintype "power_in"))
      (node (ref "U9") (pin "1") (pinfunction "VDD_1") (pintype "power_in"))
      (node (ref "U9") (pin "14") (pinfunction "VDD_14") (pintype "power_in"))
      (node (ref "U9") (pin "27") (pinfunction "VDD_27") (pintype "power_in"))
      (node (ref "U9") (pin "3") (pinfunction "VDDQ_3") (pintype "power_in"))
      (node (ref "U9") (pin "43") (pinfunction "VDDQ_43") (pintype "power_in"))
      (node (ref "U9") (pin "49") (pinfunction "VDDQ_49") (pintype "power_in"))
      (node (ref "U9") (pin "9") (pinfunction "VDDQ_9") (pintype "power_in"))
      (node (ref "Y1") (pin "4") (pinfunction "VDD_4") (pintype "power_in"))
    )
    (net (code "135") (name "GND") (class "Default")
      (node (ref "C10") (pin "2") (pinfunction "2_2") (pintype "passive"))
      (node (ref "C11") (pin "1") (pinfunction "1_1") (pintype "passive"))
      (node (ref "C12") (pin "1") (pinfunction "1_1") (pintype "passive"))
      (node (ref "C13") (pin "1") (pinfunction "1_1") (pintype "passive"))
      (node (ref "C14") (pin "1") (pinfunction "1_1") (pintype "passive"))
      (node (ref "C15") (pin "2") (pinfunction "2_2") (pintype "passive"))
      (node (ref "C16") (pin "2") (pinfunction "2_2") (pintype "passive"))
      (node (ref "C17") (pin "2") (pinfunction "2_2") (pintype "passive"))
      (node (ref "C18") (pin "2") (pinfunction "2_2") (pintype "passive"))
      (node (ref "C19") (pin "1") (pinfunction "1_1") (pintype "passive"))
      (node (ref "C20") (pin "1") (pinfunction "1_1") (pintype "passive"))
      (node (ref "C21") (pin "1") (pinfunction "1_1") (pintype "passive"))
      (node (ref "C22") (pin "1") (pinfunction "1_1") (pintype "passive"))
      (node (ref "C23") (pin "1") (pinfunction "1_1") (pintype "passive"))
      (node (ref "C24") (pin "1") (pinfunction "1_1") (pintype "passive"))
      (node (ref "C25") (pin "1") (pinfunction "1_1") (pintype "passive"))
      (node (ref "C26") (pin "1") (pinfunction "1_1") (pintype "passive"))
      (node (ref "C27") (pin "1") (pinfunction "1_1") (pintype "passive"))
      (node (ref "C28") (pin "1") (pinfunction "1_1") (pintype "passive"))
      (node (ref "C29") (pin "1") (pinfunction "1_1") (pintype "passive"))
      (node (ref "C3") (pin "1") (pinfunction "1_1") (pintype "passive"))
      (node (ref "C30") (pin "1") (pinfunction "1_1") (pintype "passive"))
      (node (ref "C31") (pin "1") (pinfunction "1_1") (pintype "passive"))
      (node (ref "C32") (pin "1") (pinfunction "1_1") (pintype "passive"))
      (node (ref "C33") (pin "1") (pinfunction "1_1") (pintype "passive"))
      (node (ref "C34") (pin "1") (pinfunction "1_1") (pintype "passive"))
      (node (ref "C35") (pin "1") (pinfunction "1_1") (pintype "passive"))
      (node (ref "C36") (pin "1") (pinfunction "1_1") (pintype "passive"))
      (node (ref "C37") (pin "1") (pinfunction "1_1") (pintype "passive"))
      (node (ref "C38") (pin "1") (pinfunction "1_1") (pintype "passive"))
      (node (ref "C39") (pin "1") (pinfunction "1_1") (pintype "passive"))
      (node (ref "C40") (pin "1") (pinfunction "1_1") (pintype "passive"))
      (node (ref "C41") (pin "1") (pinfunction "1_1") (pintype "passive"))
      (node (ref "C42") (pin "1") (pinfunction "1_1") (pintype "passive"))
      (node (ref "C43") (pin "1") (pinfunction "1_1") (pintype "passive"))
      (node (ref "C44") (pin "1") (pinfunction "1_1") (pintype "passive"))
      (node (ref "C45") (pin "1") (pinfunction "1_1") (pintype "passive"))
      (node (ref "C46") (pin "1") (pinfunction "1_1") (pintype "passive"))
      (node (ref "C47") (pin "1") (pinfunction "1_1") (pintype "passive"))
      (node (ref "C48") (pin "1") (pinfunction "1_1") (pintype "passive"))
      (node (ref "C49") (pin "1") (pinfunction "1_1") (pintype "passive"))
      (node (ref "C5") (pin "1") (pinfunction "1_1") (pintype "passive"))
      (node (ref "C50") (pin "1") (pinfunction "1_1") (pintype "passive"))
      (node (ref "C51") (pin "1") (pinfunction "1_1") (pintype "passive"))
      (node (ref "C52") (pin "1") (pinfunction "1_1") (pintype "passive"))
      (node (ref "C53") (pin "1") (pinfunction "1_1") (pintype "passive"))
      (node (ref "C54") (pin "1") (pinfunction "1_1") (pintype "passive"))
      (node (ref "C55") (pin "1") (pinfunction "1_1") (pintype "passive"))
      (node (ref "C56") (pin "1") (pinfunction "1_1") (pintype "passive"))
      (node (ref "C57") (pin "1") (pinfunction "1_1") (pintype "passive"))
      (node (ref "C58") (pin "1") (pinfunction "1_1") (pintype "passive"))
      (node (ref "C59") (pin "1") (pinfunction "1_1") (pintype "passive"))
      (node (ref "C60") (pin "1") (pinfunction "1_1") (pintype "passive"))
      (node (ref "C61") (pin "1") (pinfunction "1_1") (pintype "passive"))
      (node (ref "C62") (pin "1") (pinfunction "1_1") (pintype "passive"))
      (node (ref "C63") (pin "1") (pinfunction "1_1") (pintype "passive"))
      (node (ref "C64") (pin "1") (pinfunction "1_1") (pintype "passive"))
      (node (ref "C65") (pin "1") (pinfunction "1_1") (pintype "passive"))
      (node (ref "C66") (pin "1") (pinfunction "1_1") (pintype "passive"))
      (node (ref "C67") (pin "1") (pinfunction "1_1") (pintype "passive"))
      (node (ref "C68") (pin "1") (pinfunction "1_1") (pintype "passive"))
      (node (ref "C69") (pin "1") (pinfunction "1_1") (pintype "passive"))
      (node (ref "C7") (pin "2") (pinfunction "2_2") (pintype "passive"))
      (node (ref "C70") (pin "1") (pinfunction "1_1") (pintype "passive"))
      (node (ref "C71") (pin "1") (pinfunction "1_1") (pintype "passive"))
      (node (ref "C72") (pin "1") (pinfunction "1_1") (pintype "passive"))
      (node (ref "C73") (pin "1") (pinfunction "1_1") (pintype "passive"))
      (node (ref "C74") (pin "1") (pinfunction "1_1") (pintype "passive"))
      (node (ref "C75") (pin "1") (pinfunction "1_1") (pintype "passive"))
      (node (ref "C8") (pin "2") (pinfunction "2_2") (pintype "passive"))
      (node (ref "C9") (pin "2") (pinfunction "2_2") (pintype "passive"))
      (node (ref "D1") (pin "1") (pintype "passive"))
      (node (ref "D2") (pin "1") (pintype "passive"))
      (node (ref "D3") (pin "1") (pintype "passive"))
      (node (ref "D4") (pin "1") (pintype "passive"))
      (node (ref "J1") (pin "1") (pinfunction "GND_1") (pintype "power_in"))
      (node (ref "J2") (pin "10") (pinfunction "10_10") (pintype "passive"))
      (node (ref "J2") (pin "2") (pinfunction "2_2") (pintype "passive"))
      (node (ref "J3") (pin "10") (pinfunction "10_10") (pintype "passive"))
      (node (ref "J3") (pin "2") (pinfunction "2_2") (pintype "passive"))
      (node (ref "P1") (pin "2") (pinfunction "2_2") (pintype "passive"))
      (node (ref "P1") (pin "4") (pinfunction "4_4") (pintype "passive"))
      (node (ref "P1") (pin "6") (pinfunction "6_6") (pintype "passive"))
      (node (ref "P1") (pin "8") (pinfunction "8_8") (pintype "passive"))
      (node (ref "P2") (pin "3") (pinfunction "3_3") (pintype "passive"))
      (node (ref "P2") (pin "37") (pinfunction "37_37") (pintype "passive"))
      (node (ref "P2") (pin "38") (pinfunction "38_38") (pintype "passive"))
      (node (ref "P2") (pin "4") (pinfunction "4_4") (pintype "passive"))
      (node (ref "P3") (pin "3") (pinfunction "3_3") (pintype "passive"))
      (node (ref "P3") (pin "34") (pinfunction "34_34") (pintype "passive"))
      (node (ref "P3") (pin "35") (pinfunction "35_35") (pintype "passive"))
      (node (ref "P3") (pin "36") (pinfunction "36_36") (pintype "passive"))
      (node (ref "P3") (pin "37") (pinfunction "37_37") (pintype "passive"))
      (node (ref "P3") (pin "38") (pinfunction "38_38") (pintype "passive"))
      (node (ref "P3") (pin "4") (pinfunction "4_4") (pintype "passive"))
      (node (ref "R10") (pin "1") (pinfunction "1_1") (pintype "passive"))
      (node (ref "R12") (pin "1") (pinfunction "1_1") (pintype "passive"))
      (node (ref "R21") (pin "1") (pinfunction "1_1") (pintype "passive"))
      (node (ref "R22") (pin "1") (pinfunction "1_1") (pintype "passive"))
      (node (ref "R23") (pin "1") (pinfunction "1_1") (pintype "passive"))
      (node (ref "R24") (pin "2") (pinfunction "2_2") (pintype "passive"))
      (node (ref "R30") (pin "1") (pinfunction "1_1") (pintype "passive"))
      (node (ref "R31") (pin "1") (pinfunction "1_1") (pintype "passive"))
      (node (ref "R6") (pin "1") (pinfunction "1_1") (pintype "passive"))
      (node (ref "R7") (pin "1") (pinfunction "1_1") (pintype "passive"))
      (node (ref "R8") (pin "1") (pinfunction "1_1") (pintype "passive"))
      (node (ref "R9") (pin "1") (pinfunction "1_1") (pintype "passive"))
      (node (ref "U1") (pin "4") (pinfunction "GND_4") (pintype "power_in"))
      (node (ref "U1") (pin "EP") (pinfunction "Pad_EP") (pintype "power_in"))
      (node (ref "U2") (pin "4") (pinfunction "GND_4") (pintype "power_in"))
      (node (ref "U2") (pin "EP") (pinfunction "Pad_EP") (pintype "power_in"))
      (node (ref "U4") (pin "1") (pinfunction "GND_1") (pintype "passive"))
      (node (ref "U6") (pin "102") (pinfunction "GND_102") (pintype "power_in"))
      (node (ref "U6") (pin "105") (pinfunction "GND_105") (pintype "power_in"))
      (node (ref "U6") (pin "109") (pinfunction "GND_109") (pintype "power_in"))
      (node (ref "U6") (pin "11") (pinfunction "GND_11") (pintype "power_in"))
      (node (ref "U6") (pin "116") (pinfunction "GND_116") (pintype "power_in"))
      (node (ref "U6") (pin "120") (pinfunction "GND_120") (pintype "power_in"))
      (node (ref "U6") (pin "122") (pinfunction "GNDA4_122") (pintype "power_in"))
      (node (ref "U6") (pin "125") (pinfunction "GND_125") (pintype "power_in"))
      (node (ref "U6") (pin "130") (pinfunction "GND_130") (pintype "power_in"))
      (node (ref "U6") (pin "138") (pinfunction "GND_138") (pintype "power_in"))
      (node (ref "U6") (pin "141") (pinfunction "GND_141") (pintype "power_in"))
      (node (ref "U6") (pin "148") (pinfunction "GND_148") (pintype "power_in"))
      (node (ref "U6") (pin "149") (pinfunction "CLK7,_DIFFCLK_3n_149") (pintype "input"))
      (node (ref "U6") (pin "150") (pinfunction "CLK6,_DIFFCLK_3p_150") (pintype "input"))
      (node (ref "U6") (pin "151") (pinfunction "CLK5,_DIFFCLK_2n_151") (pintype "input"))
      (node (ref "U6") (pin "152") (pinfunction "CLK4,_DIFFCLK_2p_152") (pintype "input"))
      (node (ref "U6") (pin "156") (pinfunction "GND_156") (pintype "power_in"))
      (node (ref "U6") (pin "16") (pinfunction "GND_16") (pintype "power_in"))
      (node (ref "U6") (pin "165") (pinfunction "GND_165") (pintype "power_in"))
      (node (ref "U6") (pin "168") (pinfunction "GND_168") (pintype "power_in"))
      (node (ref "U6") (pin "172") (pinfunction "GND_172") (pintype "power_in"))
      (node (ref "U6") (pin "175") (pinfunction "GND_175") (pintype "power_in"))
      (node (ref "U6") (pin "179") (pinfunction "GNDA2_179") (pintype "power_in"))
      (node (ref "U6") (pin "182") (pinfunction "GND_182") (pintype "power_in"))
      (node (ref "U6") (pin "191") (pinfunction "GND_191") (pintype "power_in"))
      (node (ref "U6") (pin "193") (pinfunction "GND_193") (pintype "power_in"))
      (node (ref "U6") (pin "199") (pinfunction "GND_199") (pintype "power_in"))
      (node (ref "U6") (pin "2") (pinfunction "GNDA3_2") (pintype "power_in"))
      (node (ref "U6") (pin "20") (pinfunction "GND_20") (pintype "power_in"))
      (node (ref "U6") (pin "205") (pinfunction "GND_205") (pintype "power_in"))
      (node (ref "U6") (pin "208") (pinfunction "GND_208") (pintype "power_in"))
      (node (ref "U6") (pin "209") (pinfunction "CLK8,_DIFFCLK_5n_209") (pintype "input"))
      (node (ref "U6") (pin "210") (pinfunction "CLK9,_DIFFCLK_5p_210") (pintype "input"))
      (node (ref "U6") (pin "211") (pinfunction "CLK10,_DIFFCLK_4n_211") (pintype "input"))
      (node (ref "U6") (pin "212") (pinfunction "CLK11,_DIFFCLK_4p_212") (pintype "input"))
      (node (ref "U6") (pin "215") (pinfunction "GND_215") (pintype "power_in"))
      (node (ref "U6") (pin "222") (pinfunction "GND_222") (pintype "power_in"))
      (node (ref "U6") (pin "227") (pinfunction "GND_227") (pintype "power_in"))
      (node (ref "U6") (pin "229") (pinfunction "GND_229") (pintype "power_in"))
      (node (ref "U6") (pin "234") (pinfunction "GND_234") (pintype "power_in"))
      (node (ref "U6") (pin "238") (pinfunction "GND_238") (pintype "power_in"))
      (node (ref "U6") (pin "32") (pinfunction "CLK1,_DIFFCLK_0n_32") (pintype "input"))
      (node (ref "U6") (pin "33") (pinfunction "CLK2,_DIFFCLK_1p_33") (pintype "input"))
      (node (ref "U6") (pin "34") (pinfunction "CLK3,_DIFFCLK_1n_34") (pintype "input"))
      (node (ref "U6") (pin "36") (pinfunction "GND_36") (pintype "power_in"))
      (node (ref "U6") (pin "42") (pinfunction "GND_42") (pintype "power_in"))
      (node (ref "U6") (pin "48") (pinfunction "GND_48") (pintype "power_in"))
      (node (ref "U6") (pin "5") (pinfunction "GND_5") (pintype "power_in"))
      (node (ref "U6") (pin "54") (pinfunction "GND_54") (pintype "power_in"))
      (node (ref "U6") (pin "59") (pinfunction "GNDA1_59") (pintype "power_in"))
      (node (ref "U6") (pin "62") (pinfunction "GND_62") (pintype "power_in"))
      (node (ref "U6") (pin "65") (pinfunction "GND_65") (pintype "power_in"))
      (node (ref "U6") (pin "67") (pinfunction "GND_67") (pintype "power_in"))
      (node (ref "U6") (pin "72") (pinfunction "GND_72") (pintype "power_in"))
      (node (ref "U6") (pin "75") (pinfunction "GND_75") (pintype "power_in"))
      (node (ref "U6") (pin "79") (pinfunction "GND_79") (pintype "power_in"))
      (node (ref "U6") (pin "8") (pinfunction "GND_8") (pintype "power_in"))
      (node (ref "U6") (pin "86") (pinfunction "GND_86") (pintype "power_in"))
      (node (ref "U6") (pin "89") (pinfunction "CLK15,_DIFFCLK_6p_89") (pintype "input"))
      (node (ref "U6") (pin "90") (pinfunction "CLK14,_DIFFCLK_6n_90") (pintype "input"))
      (node (ref "U6") (pin "91") (pinfunction "CLK13,_DIFFCLK_7p_91") (pintype "input"))
      (node (ref "U6") (pin "92") (pinfunction "CLK12,_DIFFCLK_7n_92") (pintype "input"))
      (node (ref "U6") (pin "97") (pinfunction "GND_97") (pintype "power_in"))
      (node (ref "U7") (pin "A1") (pinfunction "VSS_A1") (pintype "power_in"))
      (node (ref "U7") (pin "B3") (pinfunction "VSS_B3") (pintype "power_in"))
      (node (ref "U7") (pin "C1") (pinfunction "VSSQ_C1") (pintype "power_in"))
      (node (ref "U7") (pin "E5") (pinfunction "VSSQ_E5") (pintype "power_in"))
      (node (ref "U8") (pin "4") (pinfunction "VSS_4") (pintype "power_in"))
      (node (ref "U9") (pin "12") (pinfunction "VSSQ_12") (pintype "power_in"))
      (node (ref "U9") (pin "28") (pinfunction "VSS_28") (pintype "power_in"))
      (node (ref "U9") (pin "41") (pinfunction "VSS_41") (pintype "power_in"))
      (node (ref "U9") (pin "46") (pinfunction "VSSQ_46") (pintype "power_in"))
      (node (ref "U9") (pin "52") (pinfunction "VSSQ_52") (pintype "power_in"))
      (node (ref "U9") (pin "54") (pinfunction "VSS_54") (pintype "power_in"))
      (node (ref "U9") (pin "6") (pinfunction "VSSQ_6") (pintype "power_in"))
      (node (ref "Y1") (pin "1") (pinfunction "TRI_1") (pintype "input"))
      (node (ref "Y1") (pin "2") (pinfunction "GND_2") (pintype "power_in"))
    )
    (net (code "136") (name "Net-(C4-Pad1)") (class "Default")
      (node (ref "C4") (pin "1") (pinfunction "1_1") (pintype "passive"))
      (node (ref "R9") (pin "2") (pinfunction "2_2") (pintype "passive"))
    )
    (net (code "137") (name "Net-(C6-Pad1)") (class "Default")
      (node (ref "C6") (pin "1") (pinfunction "1_1") (pintype "passive"))
      (node (ref "R10") (pin "2") (pinfunction "2_2") (pintype "passive"))
    )
    (net (code "138") (name "Net-(D5-K)") (class "Default")
      (node (ref "D5") (pin "2") (pinfunction "K_2") (pintype "passive"))
      (node (ref "R30") (pin "2") (pinfunction "2_2") (pintype "passive"))
    )
    (net (code "139") (name "Net-(D6-K)") (class "Default")
      (node (ref "D6") (pin "2") (pinfunction "K_2") (pintype "passive"))
      (node (ref "R31") (pin "2") (pinfunction "2_2") (pintype "passive"))
    )
    (net (code "140") (name "Net-(U1-BST)") (class "Default")
      (node (ref "C1") (pin "2") (pinfunction "2_2") (pintype "passive"))
      (node (ref "U1") (pin "1") (pinfunction "BST_1") (pintype "passive"))
    )
    (net (code "141") (name "Net-(U1-COMP)") (class "Default")
      (node (ref "C4") (pin "2") (pinfunction "2_2") (pintype "passive"))
      (node (ref "U1") (pin "6") (pinfunction "COMP_6") (pintype "passive"))
    )
    (net (code "142") (name "Net-(U1-EN)") (class "Default")
      (node (ref "R2") (pin "1") (pinfunction "1_1") (pintype "passive"))
      (node (ref "U1") (pin "7") (pinfunction "EN_7") (pintype "input"))
    )
    (net (code "143") (name "Net-(U1-FB)") (class "Default")
      (node (ref "R4") (pin "2") (pinfunction "2_2") (pintype "passive"))
      (node (ref "R7") (pin "2") (pinfunction "2_2") (pintype "passive"))
      (node (ref "U1") (pin "5") (pinfunction "FB_5") (pintype "passive"))
    )
    (net (code "144") (name "Net-(U1-SS)") (class "Default")
      (node (ref "C3") (pin "2") (pinfunction "2_2") (pintype "passive"))
      (node (ref "U1") (pin "8") (pinfunction "SS_8") (pintype "passive"))
    )
    (net (code "145") (name "Net-(U1-SW)") (class "Default")
      (node (ref "C1") (pin "1") (pinfunction "1_1") (pintype "passive"))
      (node (ref "L1") (pin "1") (pinfunction "1_1") (pintype "passive"))
      (node (ref "U1") (pin "3") (pinfunction "SW_3") (pintype "power_in"))
    )
    (net (code "146") (name "Net-(U2-BST)") (class "Default")
      (node (ref "C2") (pin "2") (pinfunction "2_2") (pintype "passive"))
      (node (ref "U2") (pin "1") (pinfunction "BST_1") (pintype "passive"))
    )
    (net (code "147") (name "Net-(U2-COMP)") (class "Default")
      (node (ref "C6") (pin "2") (pinfunction "2_2") (pintype "passive"))
      (node (ref "U2") (pin "6") (pinfunction "COMP_6") (pintype "passive"))
    )
    (net (code "148") (name "Net-(U2-EN)") (class "Default")
      (node (ref "R3") (pin "1") (pinfunction "1_1") (pintype "passive"))
      (node (ref "U2") (pin "7") (pinfunction "EN_7") (pintype "input"))
    )
    (net (code "149") (name "Net-(U2-FB)") (class "Default")
      (node (ref "R5") (pin "2") (pinfunction "2_2") (pintype "passive"))
      (node (ref "R8") (pin "2") (pinfunction "2_2") (pintype "passive"))
      (node (ref "U2") (pin "5") (pinfunction "FB_5") (pintype "passive"))
    )
    (net (code "150") (name "Net-(U2-SS)") (class "Default")
      (node (ref "C5") (pin "2") (pinfunction "2_2") (pintype "passive"))
      (node (ref "U2") (pin "8") (pinfunction "SS_8") (pintype "passive"))
    )
    (net (code "151") (name "Net-(U2-SW)") (class "Default")
      (node (ref "C2") (pin "1") (pinfunction "1_1") (pintype "passive"))
      (node (ref "L2") (pin "1") (pinfunction "1_1") (pintype "passive"))
      (node (ref "U2") (pin "3") (pinfunction "SW_3") (pintype "power_in"))
    )
    (net (code "152") (name "Net-(U3-ADJ)") (class "Default")
      (node (ref "R1") (pin "1") (pinfunction "1_1") (pintype "passive"))
      (node (ref "R6") (pin "2") (pinfunction "2_2") (pintype "passive"))
      (node (ref "U3") (pin "1") (pinfunction "ADJ_1") (pintype "passive"))
    )
    (net (code "153") (name "Net-(U5-ADJUST)") (class "Default")
      (node (ref "R11") (pin "1") (pinfunction "1_1") (pintype "passive"))
      (node (ref "R12") (pin "2") (pinfunction "2_2") (pintype "passive"))
      (node (ref "U5") (pin "1") (pinfunction "ADJUST_1") (pintype "passive"))
    )
    (net (code "154") (name "Net-(U8-HOLD#)") (class "Default")
      (node (ref "R14") (pin "1") (pinfunction "1_1") (pintype "passive"))
      (node (ref "U8") (pin "3") (pinfunction "W#_3") (pintype "input"))
      (node (ref "U8") (pin "7") (pinfunction "HOLD#_7") (pintype "input"))
    )
    (net (code "155") (name "VIN") (class "Default")
      (node (ref "C7") (pin "1") (pinfunction "1_1") (pintype "passive"))
      (node (ref "J1") (pin "3") (pinfunction "Positive_3") (pintype "power_in"))
      (node (ref "P1") (pin "7") (pinfunction "7_7") (pintype "passive"))
      (node (ref "R2") (pin "2") (pinfunction "2_2") (pintype "passive"))
      (node (ref "R3") (pin "2") (pinfunction "2_2") (pintype "passive"))
      (node (ref "U1") (pin "2") (pinfunction "IN_2") (pintype "power_in"))
      (node (ref "U2") (pin "2") (pinfunction "IN_2") (pintype "power_in"))
      (node (ref "U5") (pin "3") (pinfunction "VIN_3") (pintype "power_in"))
    )
    (net (code "156") (name "unconnected-(J1-Positive_In-Pad2)") (class "Default")
      (node (ref "J1") (pin "2") (pinfunction "Positive_In_2") (pintype "power_in"))
    )
    (net (code "157") (name "unconnected-(J3-Pad6)") (class "Default")
      (node (ref "J3") (pin "6") (pinfunction "6_6") (pintype "passive"))
    )
    (net (code "158") (name "unconnected-(J3-Pad7)") (class "Default")
      (node (ref "J3") (pin "7") (pinfunction "7_7") (pintype "passive"))
    )
    (net (code "159") (name "unconnected-(J3-Pad8)") (class "Default")
      (node (ref "J3") (pin "8") (pinfunction "8_8") (pintype "passive"))
    )
    (net (code "160") (name "unconnected-(U7-CK#-PadB1)") (class "Default")
      (node (ref "U7") (pin "B1") (pinfunction "CK#_B1") (pintype "input"))
    )
    (net (code "161") (name "unconnected-(U7-RFU-PadA2)") (class "Default")
      (node (ref "U7") (pin "A2") (pinfunction "RFU_A2") (pintype "passive"))
    )
    (net (code "162") (name "unconnected-(U7-RFU-PadA5)") (class "Default")
      (node (ref "U7") (pin "A5") (pinfunction "RFU_A5") (pintype "passive"))
    )
    (net (code "163") (name "unconnected-(U7-RFU-PadB5)") (class "Default")
      (node (ref "U7") (pin "B5") (pinfunction "RFU_B5") (pintype "passive"))
    )
    (net (code "164") (name "unconnected-(U7-RFU-PadC2)") (class "Default")
      (node (ref "U7") (pin "C2") (pinfunction "RFU_C2") (pintype "passive"))
    )
    (net (code "165") (name "unconnected-(U7-RFU-PadC5)") (class "Default")
      (node (ref "U7") (pin "C5") (pinfunction "RFU_C5") (pintype "passive"))
    )
    (net (code "166") (name "unconnected-(U9A-NC-Pad40)") (class "Default")
      (node (ref "U9") (pin "40") (pinfunction "NC_40") (pintype "passive"))
    )
  )
)
